# SCH_MKA-Lite-Pi-Interface.net
KiCad netlist of a schematic drawn in EasyEDA
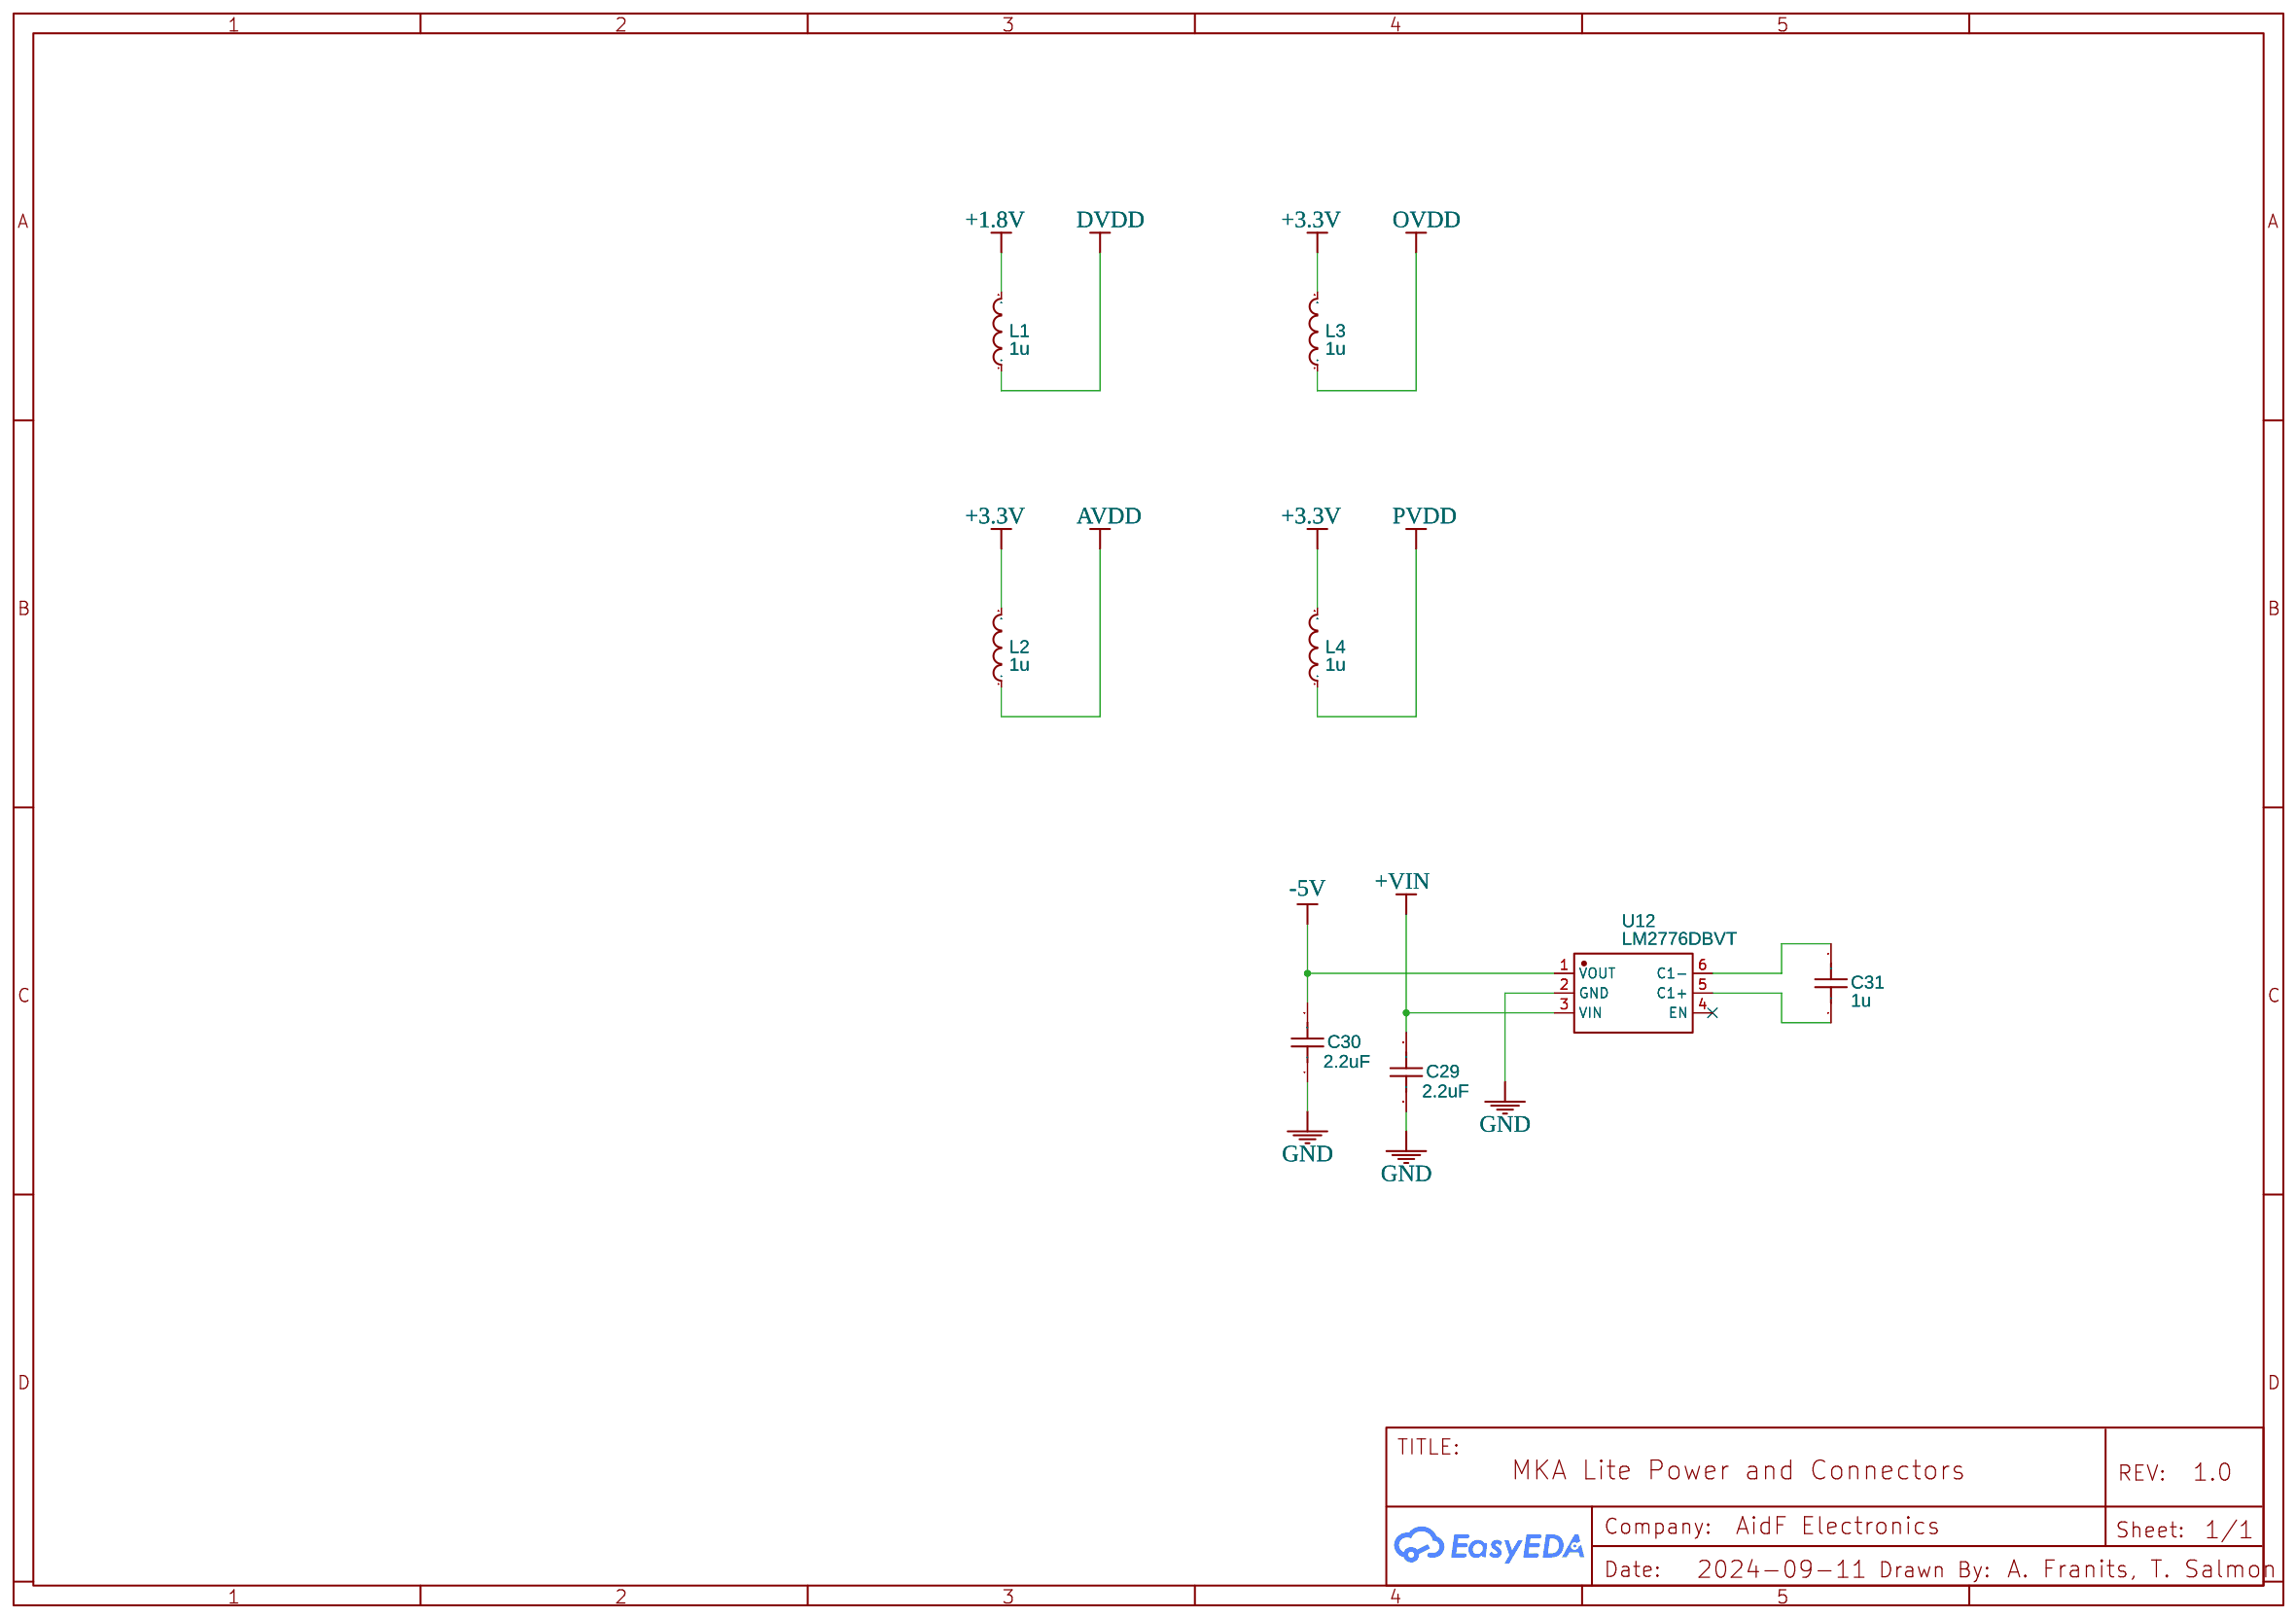
[diagram p0: Power and Connectors]
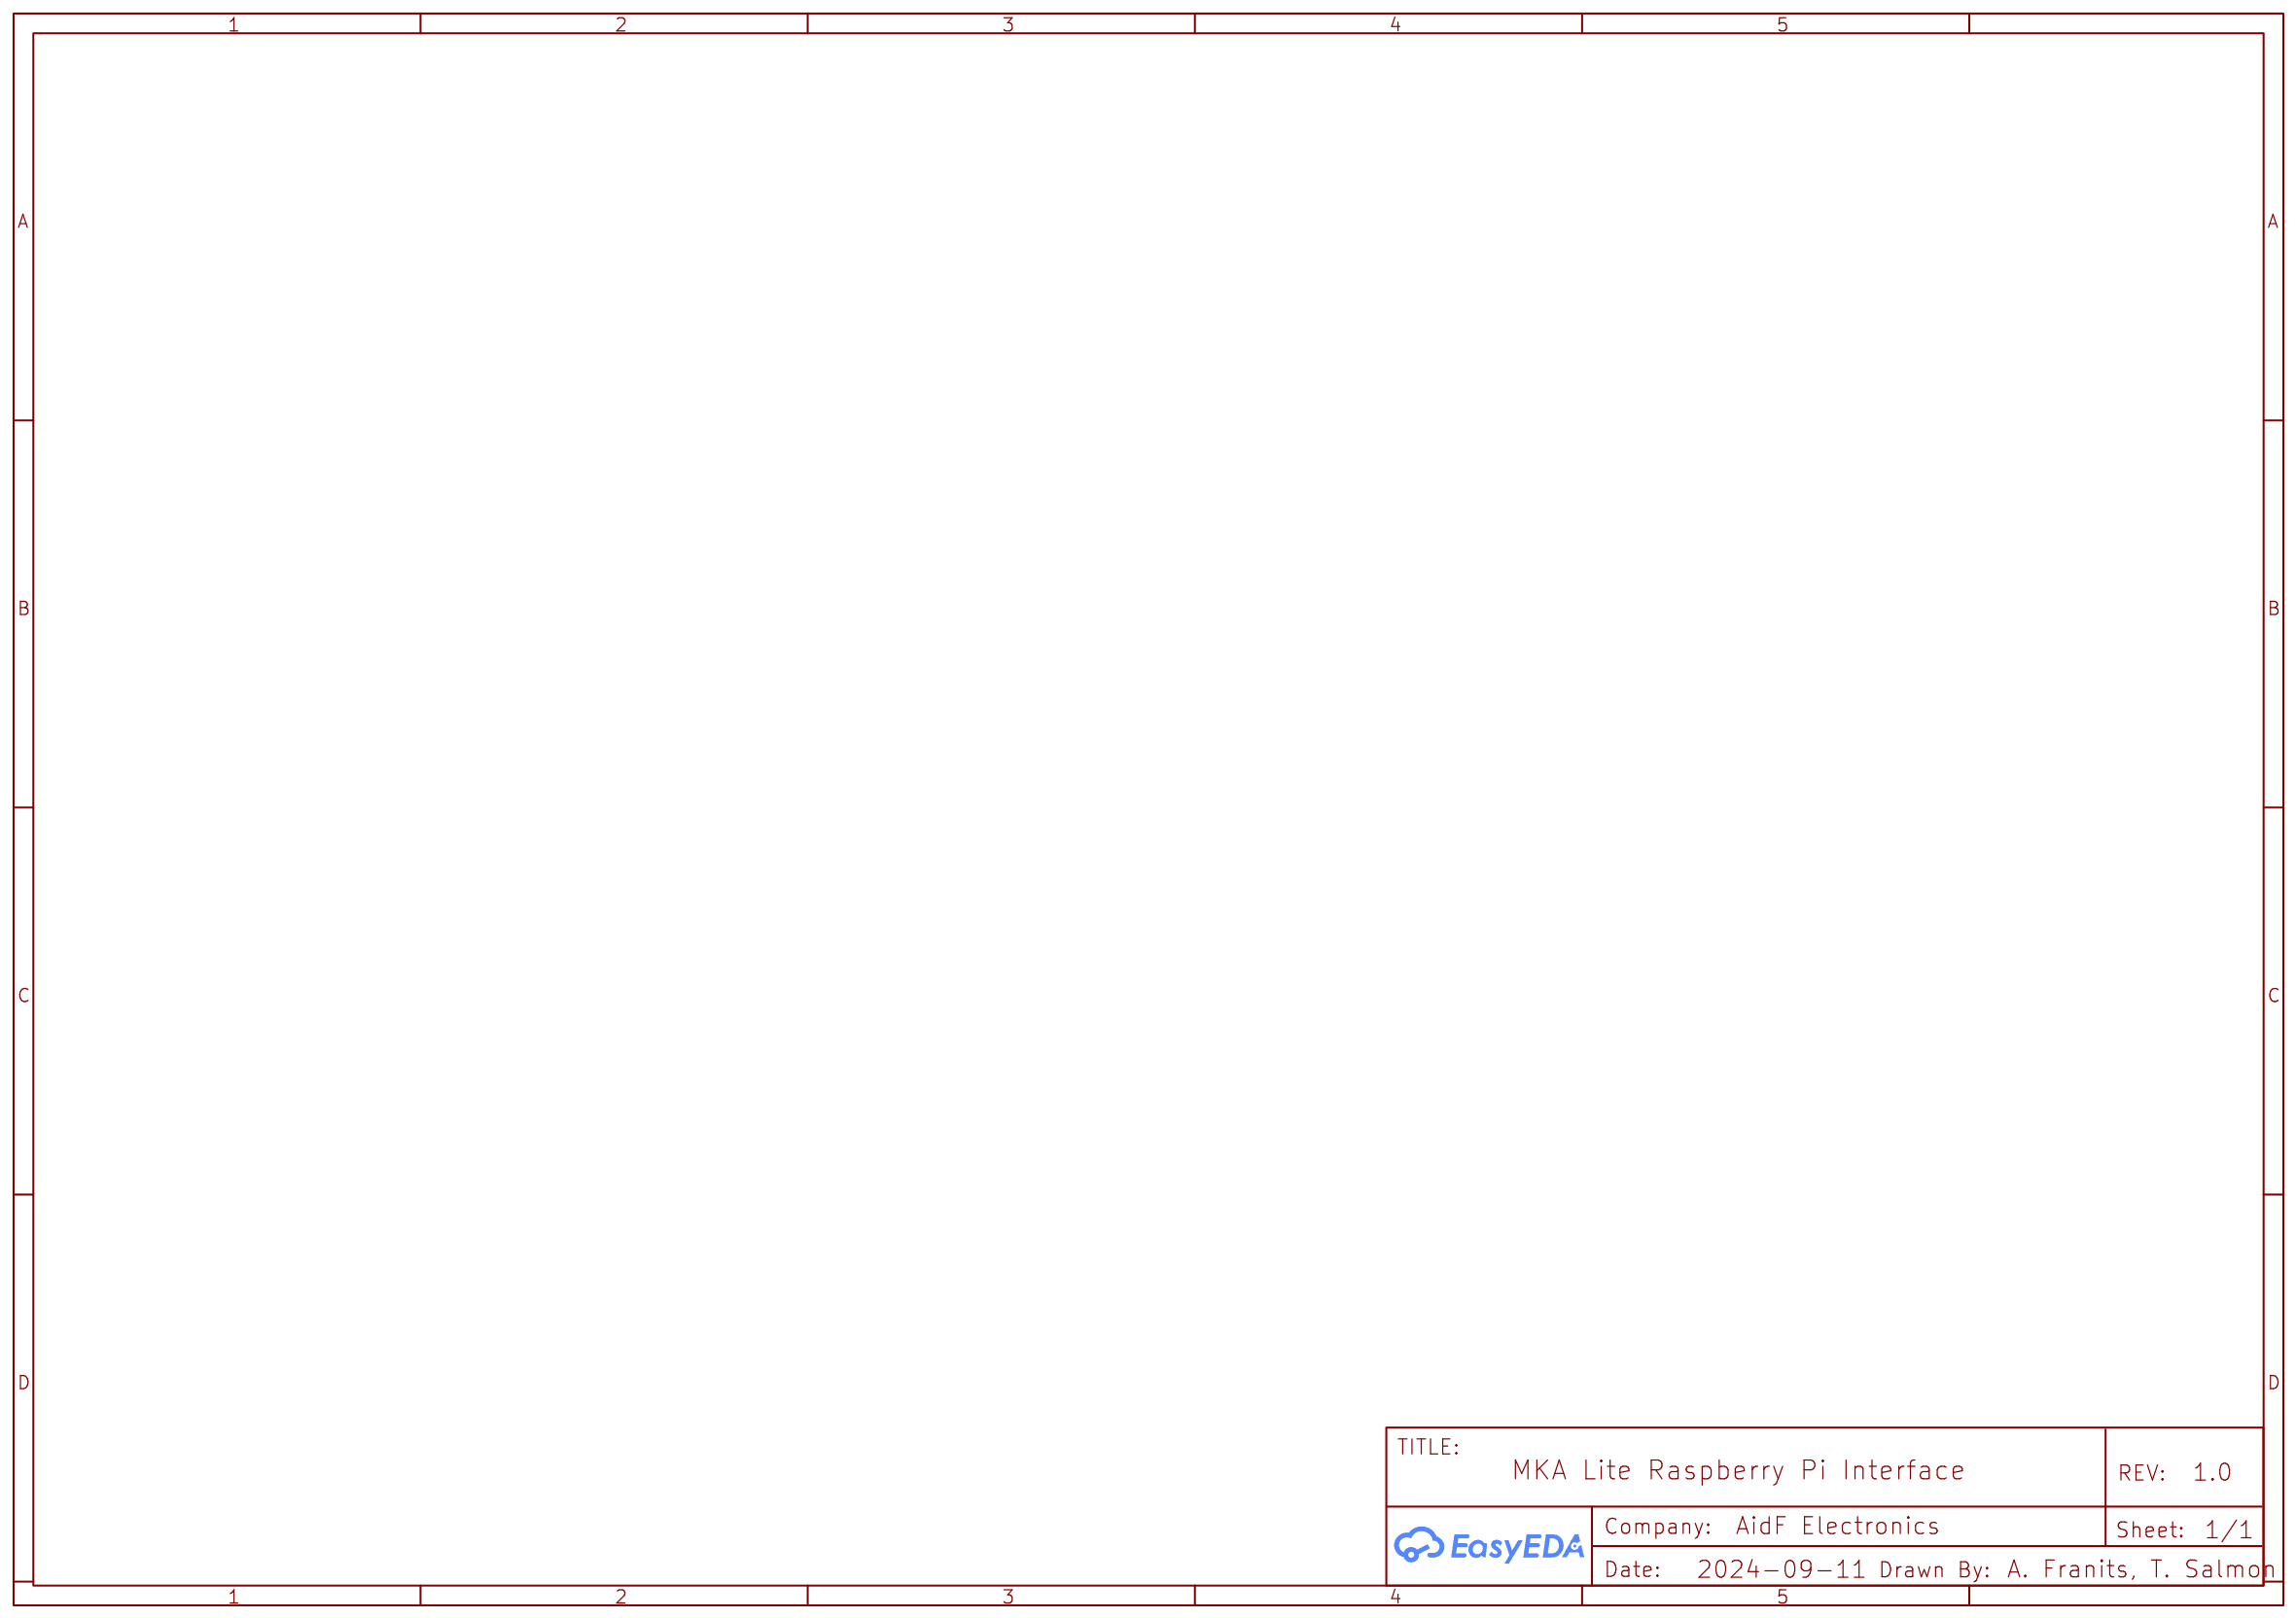
[diagram p1: Raspberry Pi CM4 Interface]
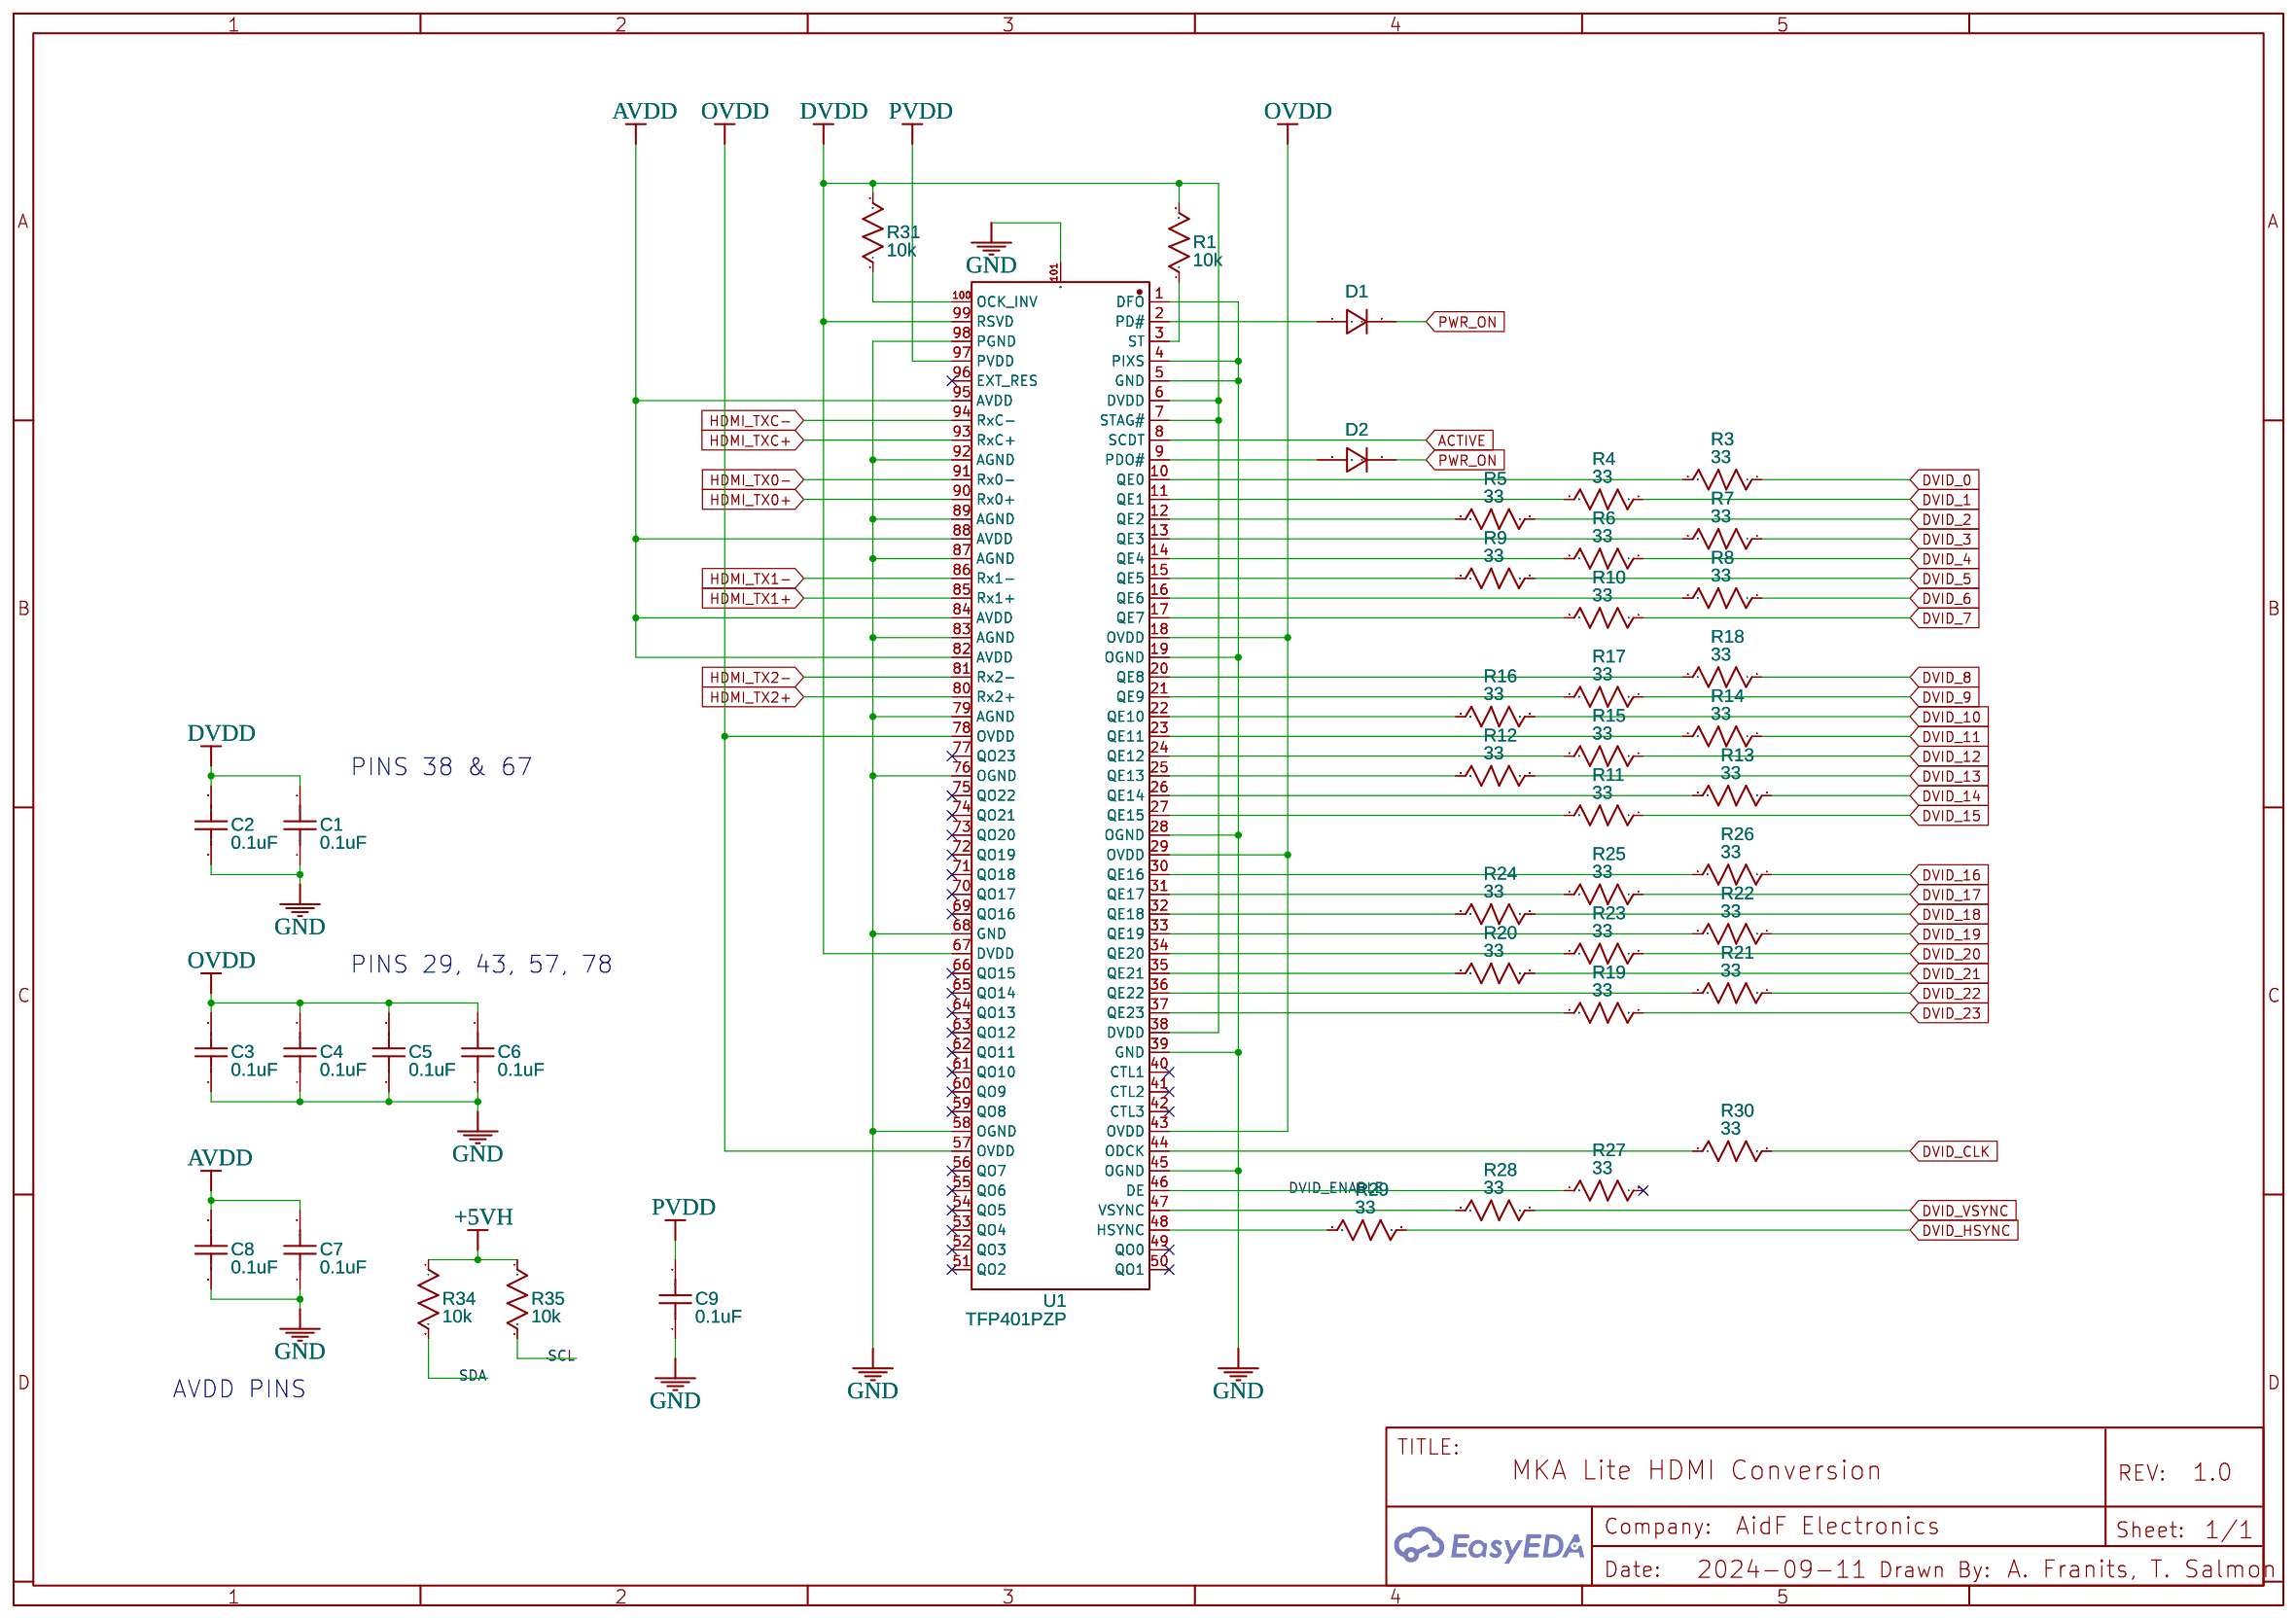
[diagram p2: HDMI Inlet]
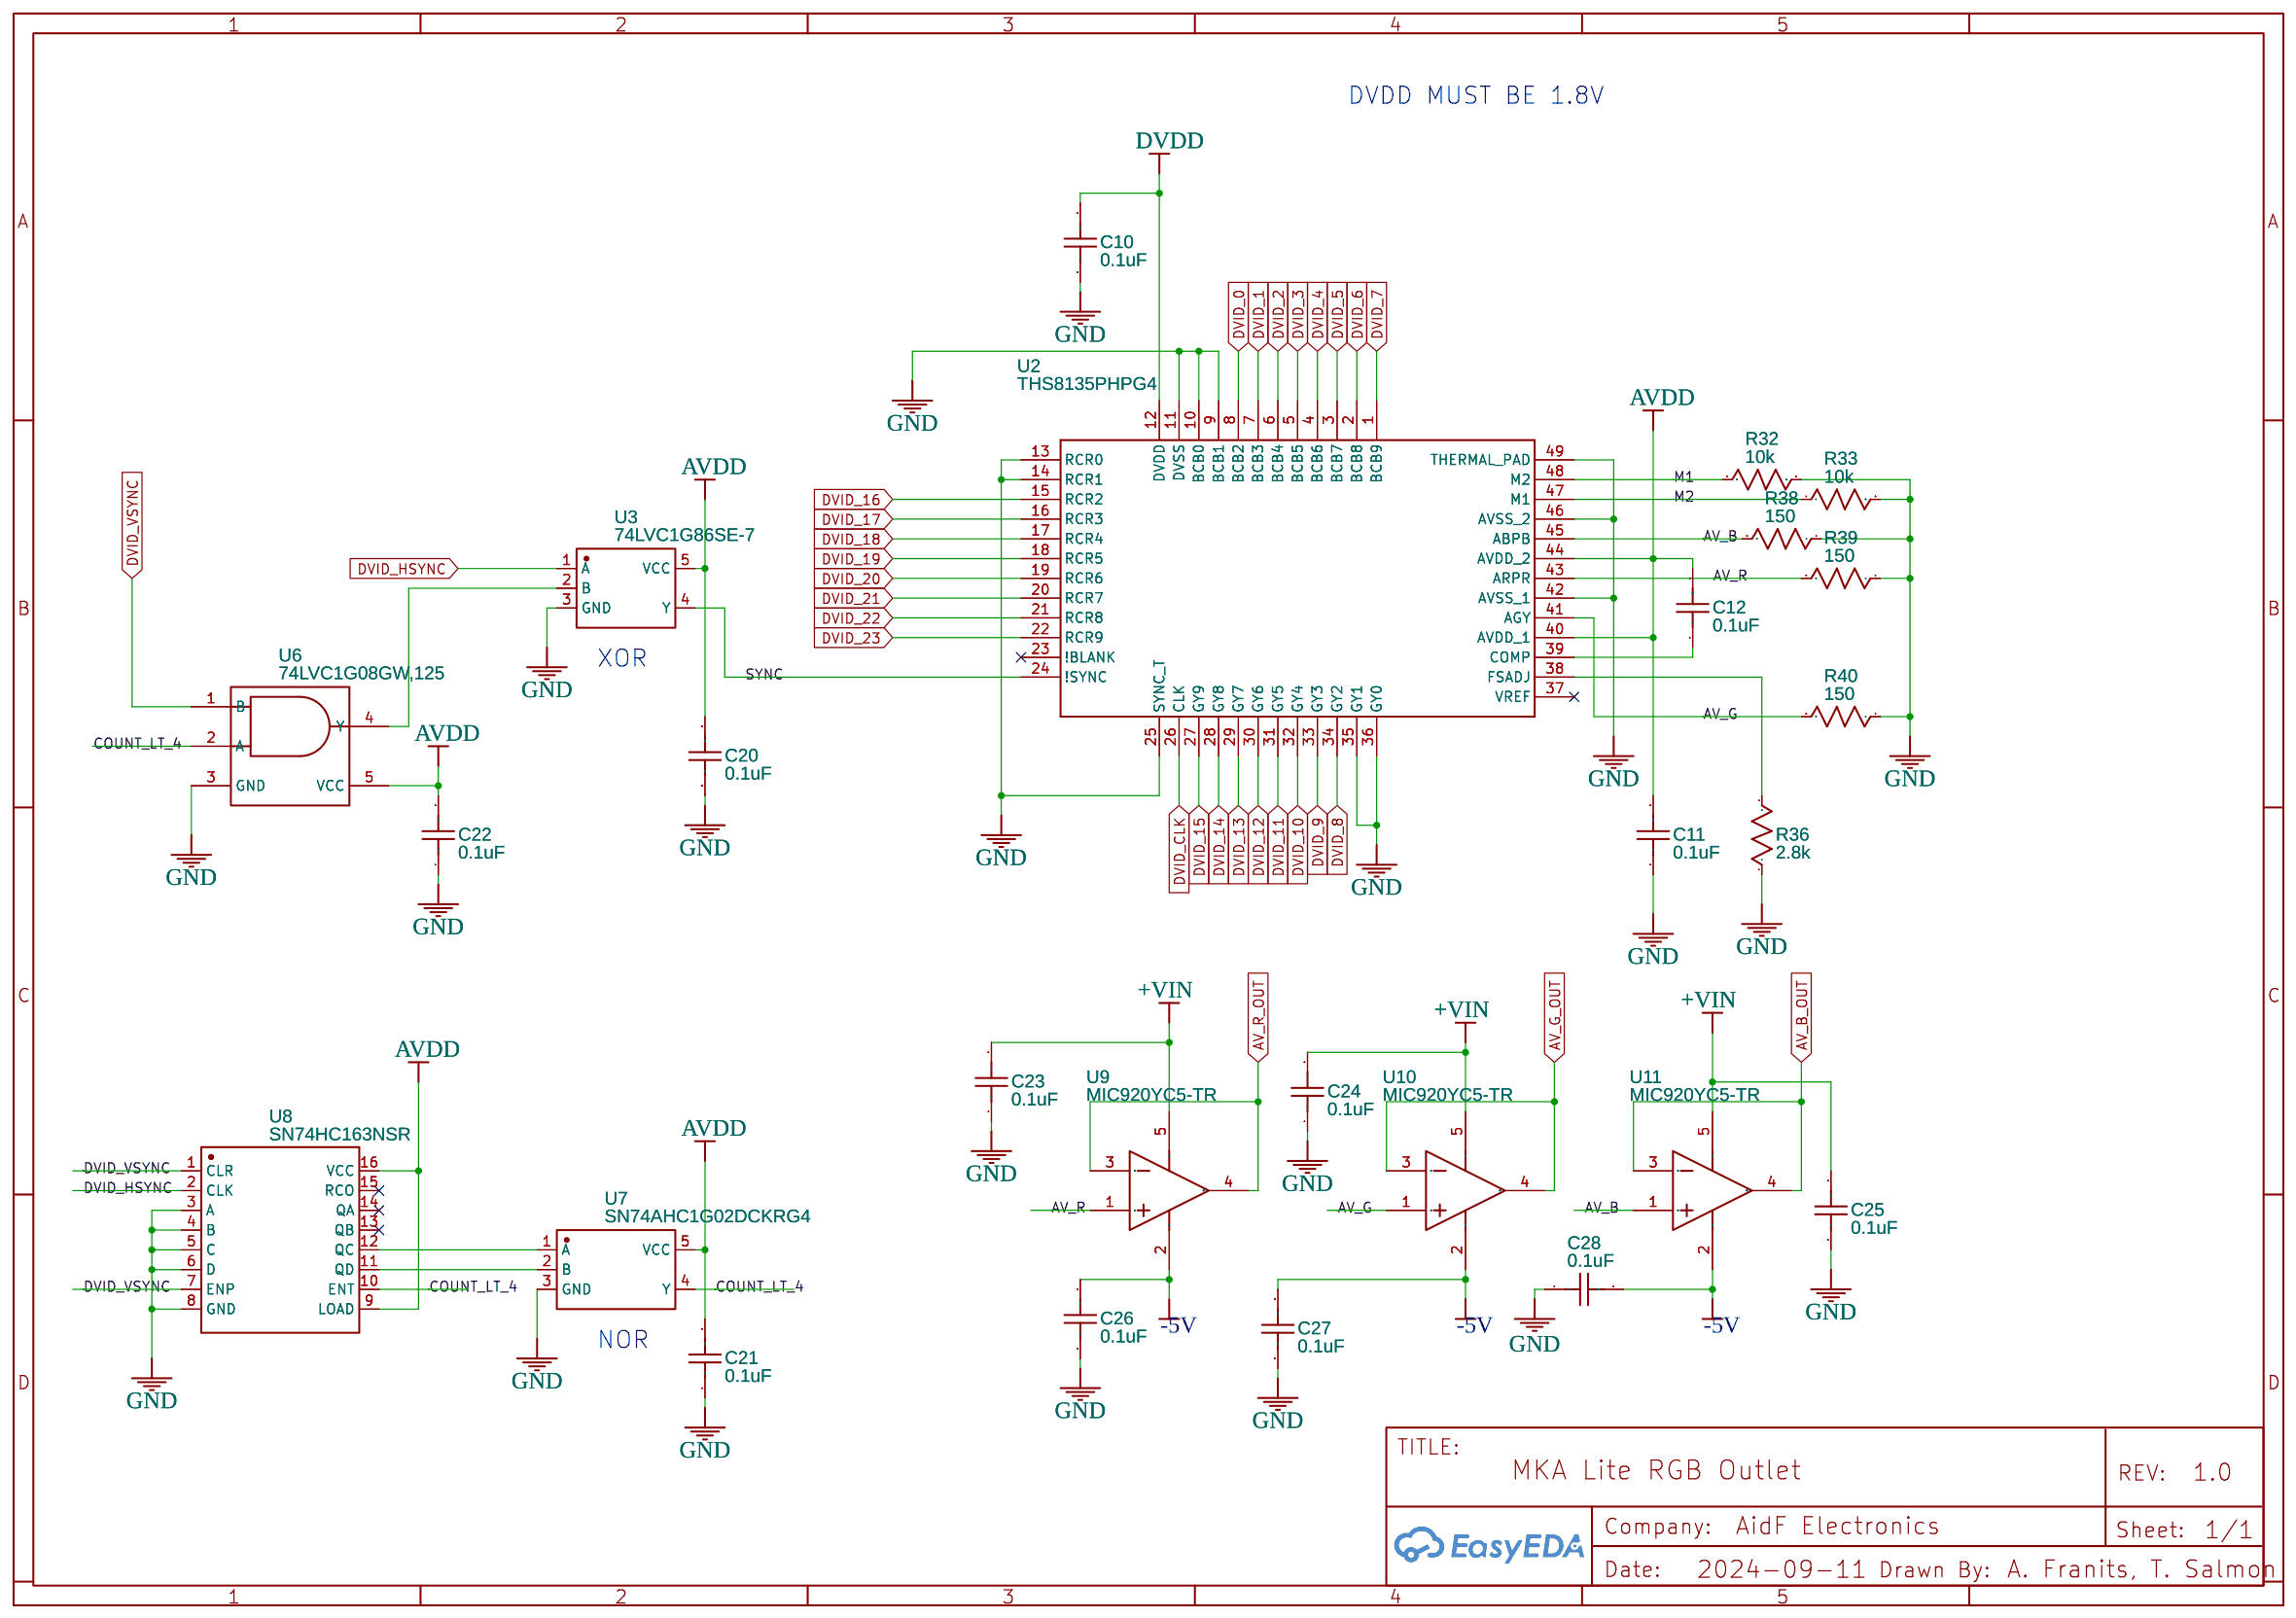
[diagram p3: RGB Outlet]
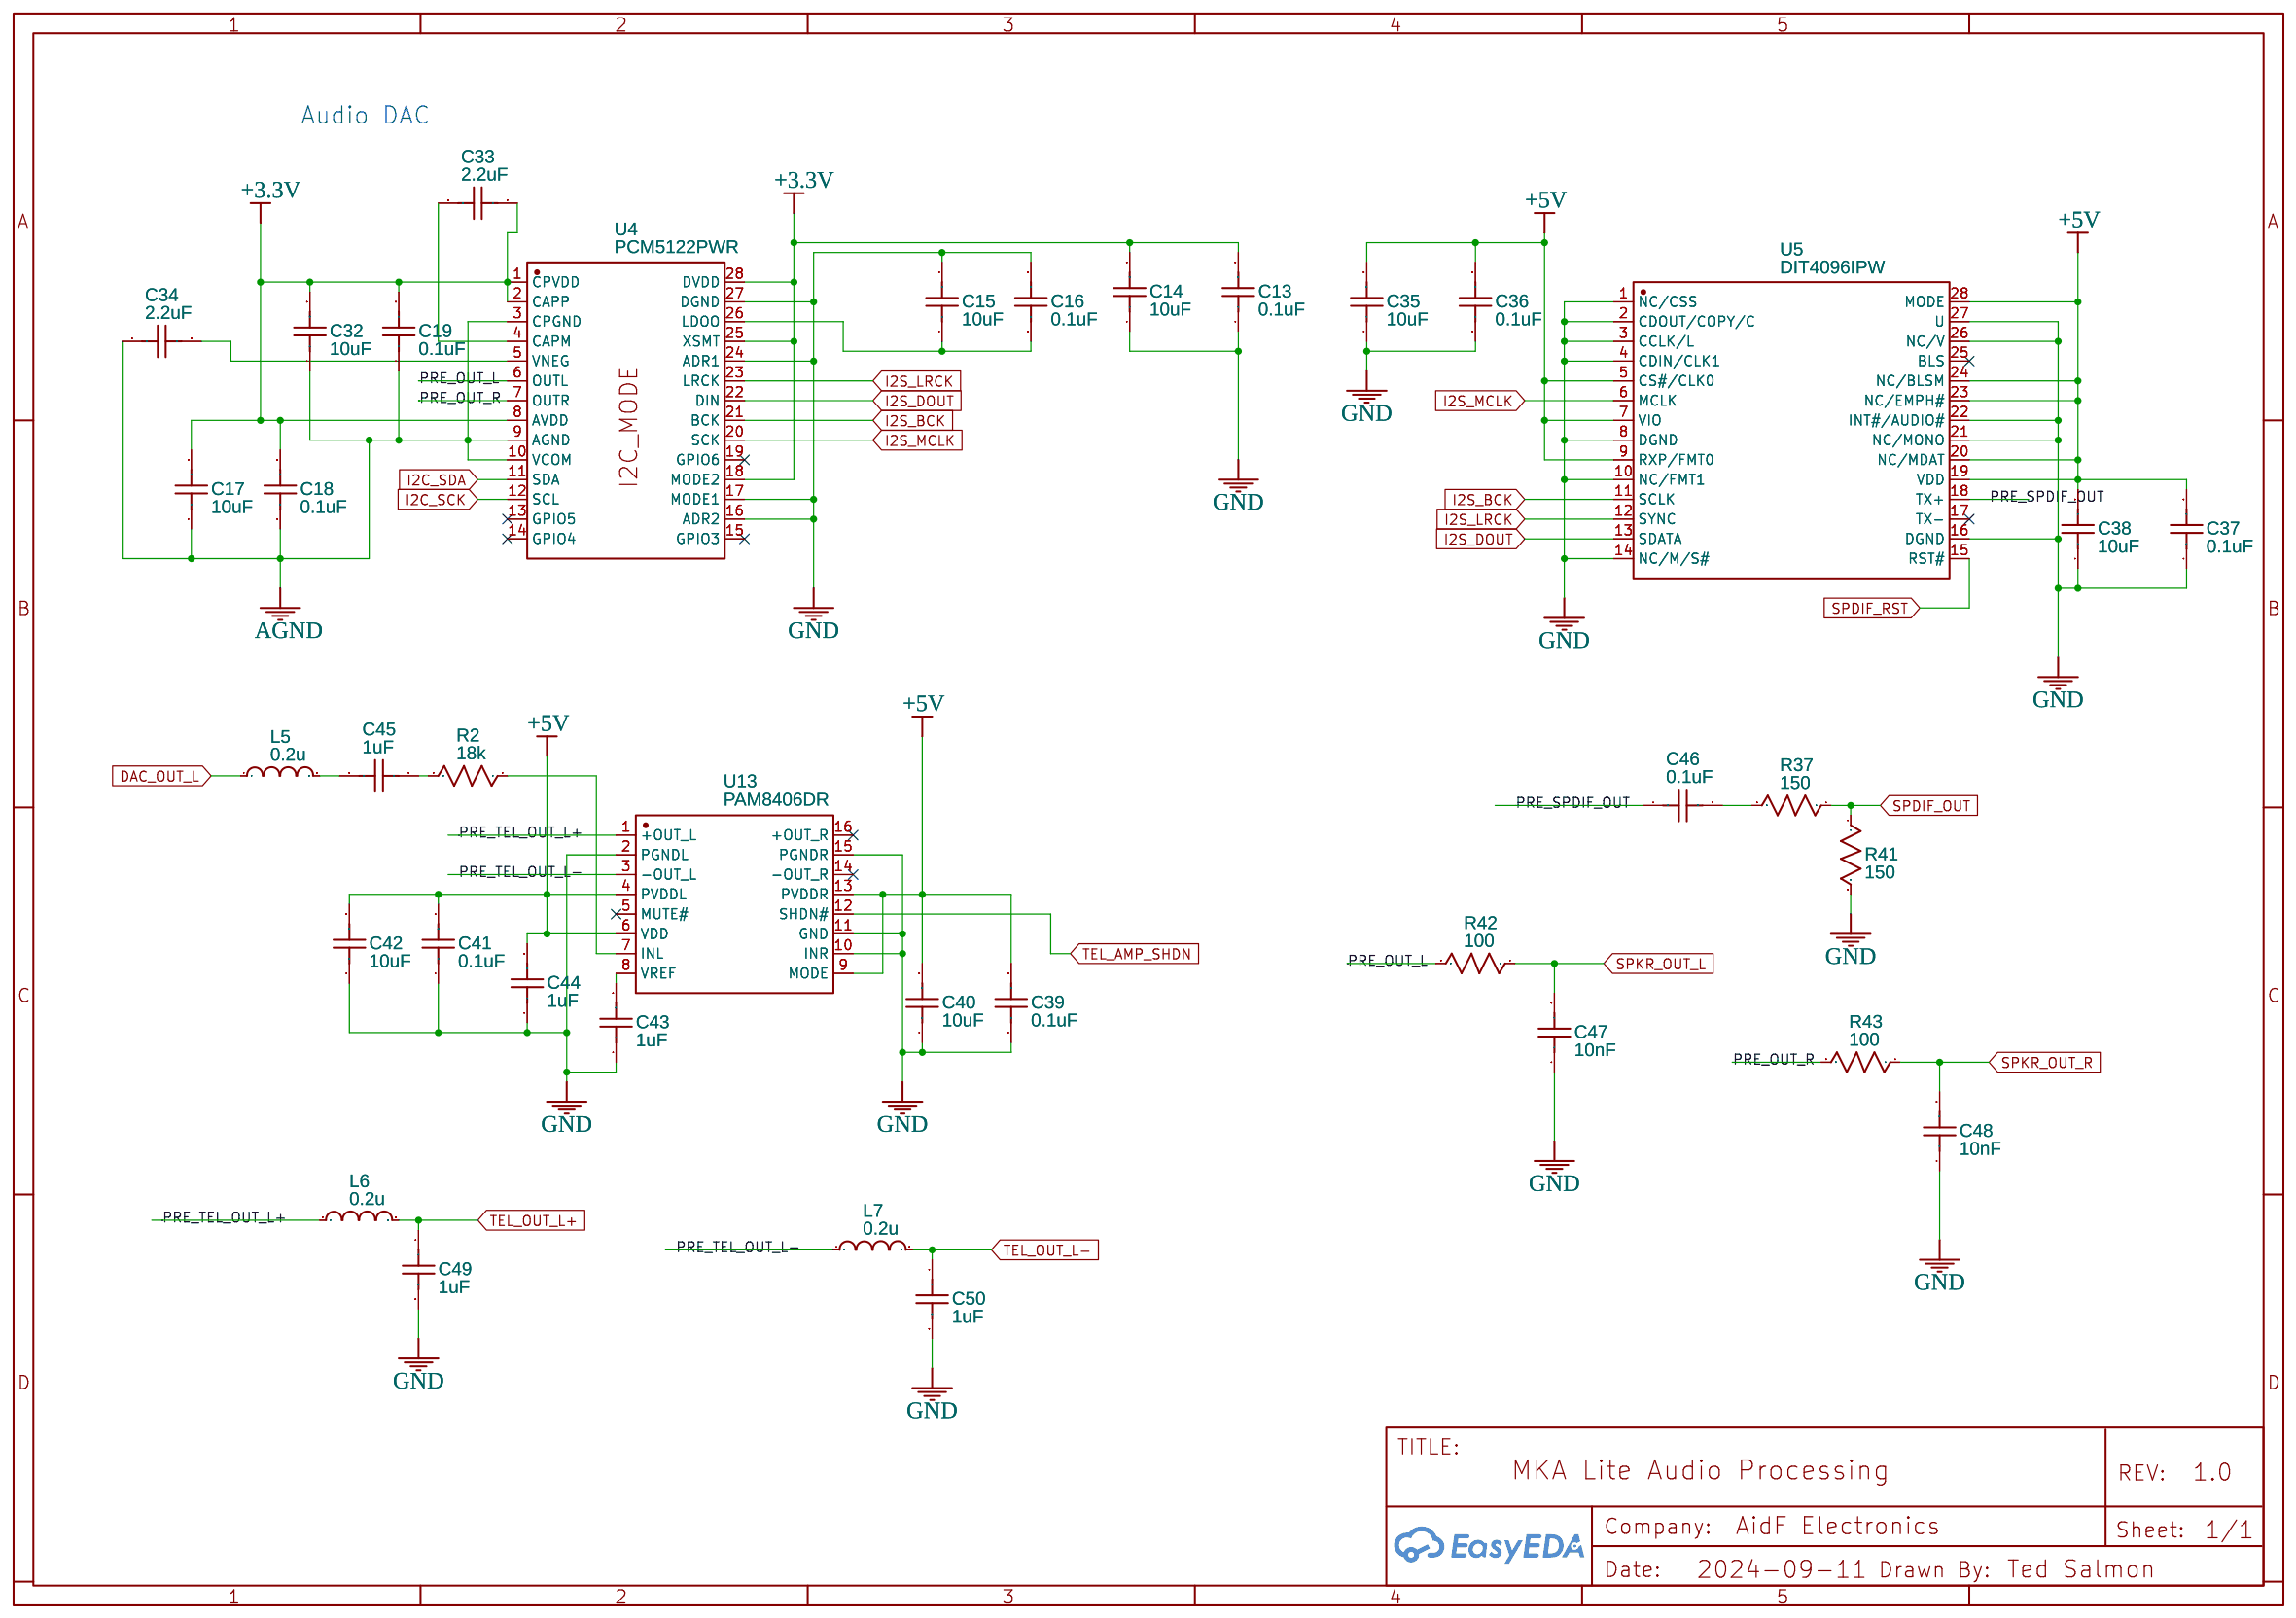
[diagram p4: Audio Processing]

(export (version "E")
  (design (tool "Eeschema 10.0.6"))
  (components
    (comp (ref "C29")
      (value "2.2uF")
      (fields
        (field (name "Manufacturer Part") "C1608X5R1E225K080AB")
        (field (name "Manufacturer") "TDK Corporation")
      )
      (libsource (lib "") (part "C_0603_US"))
    )
    (comp (ref "C30")
      (value "2.2uF")
      (fields
        (field (name "Manufacturer Part") "C1608X5R1E225K080AB")
        (field (name "Manufacturer") "TDK Corporation")
      )
      (libsource (lib "") (part "C_0603_US"))
    )
    (comp (ref "C31")
      (value "1u")
      (fields
        (field (name "Manufacturer Part") "CL10A105KB8NNNC")
        (field (name "Manufacturer") "Samsung Electro-Mechanics")
      )
      (libsource (lib "") (part "C_0603_US"))
    )
    (comp (ref "L1")
      (value "1u")
      (fields
        (field (name "Manufacturer Part") "BLM18RK601SN1D")
        (field (name "Manufacturer") "Murata Electronics")
      )
      (libsource (lib "") (part "L0603_US_1"))
    )
    (comp (ref "L2")
      (value "1u")
      (fields
        (field (name "Manufacturer Part") "BLM18RK601SN1D")
        (field (name "Manufacturer") "Murata Electronics")
      )
      (libsource (lib "") (part "L0603_US"))
    )
    (comp (ref "L3")
      (value "1u")
      (fields
        (field (name "Manufacturer Part") "BLM18RK601SN1D")
        (field (name "Manufacturer") "Murata Electronics")
      )
      (libsource (lib "") (part "L0603_US_1"))
    )
    (comp (ref "L4")
      (value "1u")
      (fields
        (field (name "Manufacturer Part") "BLM18RK601SN1D")
        (field (name "Manufacturer") "Murata Electronics")
      )
      (libsource (lib "") (part "L0603_US"))
    )
    (comp (ref "U12")
      (value "LM2776DBVT")
      (fields (field (name "Manufacturer") "TI(德州仪器)"))
      (libsource (lib "") (part "LM2776DBVT"))
    )
    (comp (ref "C1")
      (value "0.1uF")
      (fields
        (field (name "Manufacturer Part") "0603B104K101CT")
        (field (name "Manufacturer") "Walsin Technology Corporation")
      )
      (libsource (lib "") (part "C_0603_US"))
    )
    (comp (ref "C2")
      (value "0.1uF")
      (fields
        (field (name "Manufacturer Part") "0603B104K101CT")
        (field (name "Manufacturer") "Walsin Technology Corporation")
      )
      (libsource (lib "") (part "C_0603_US"))
    )
    (comp (ref "C3")
      (value "0.1uF")
      (fields
        (field (name "Manufacturer Part") "0603B104K101CT")
        (field (name "Manufacturer") "Walsin Technology Corporation")
      )
      (libsource (lib "") (part "C_0603_US"))
    )
    (comp (ref "C4")
      (value "0.1uF")
      (fields
        (field (name "Manufacturer Part") "0603B104K101CT")
        (field (name "Manufacturer") "Walsin Technology Corporation")
      )
      (libsource (lib "") (part "C_0603_US"))
    )
    (comp (ref "C5")
      (value "0.1uF")
      (fields
        (field (name "Manufacturer Part") "0603B104K101CT")
        (field (name "Manufacturer") "Walsin Technology Corporation")
      )
      (libsource (lib "") (part "C_0603_US"))
    )
    (comp (ref "C6")
      (value "0.1uF")
      (fields
        (field (name "Manufacturer Part") "0603B104K101CT")
        (field (name "Manufacturer") "Walsin Technology Corporation")
      )
      (libsource (lib "") (part "C_0603_US"))
    )
    (comp (ref "C7")
      (value "0.1uF")
      (fields
        (field (name "Manufacturer Part") "0603B104K101CT")
        (field (name "Manufacturer") "Walsin Technology Corporation")
      )
      (libsource (lib "") (part "C_0603_US"))
    )
    (comp (ref "C8")
      (value "0.1uF")
      (fields
        (field (name "Manufacturer Part") "0603B104K101CT")
        (field (name "Manufacturer") "Walsin Technology Corporation")
      )
      (libsource (lib "") (part "C_0603_US"))
    )
    (comp (ref "C9")
      (value "0.1uF")
      (fields
        (field (name "Manufacturer Part") "0603B104K101CT")
        (field (name "Manufacturer") "Walsin Technology Corporation")
      )
      (libsource (lib "") (part "C_0603_US"))
    )
    (comp (ref "D1")
      (value "SD103AWS-TP")
      (fields (field (name "Manufacturer") "Micro Commercial Co"))
      (libsource (lib "") (part "1N4148"))
    )
    (comp (ref "D2")
      (value "SD103AWS-TP")
      (fields (field (name "Manufacturer") "Micro Commercial Co"))
      (libsource (lib "") (part "1N4148"))
    )
    (comp (ref "R1")
      (value "10k")
      (fields
        (field (name "Manufacturer Part") "ESR03EZPJ103")
        (field (name "Manufacturer") "Rohm Semiconductor")
      )
      (libsource (lib "") (part "R_0603_US_2"))
    )
    (comp (ref "R3")
      (value "33")
      (fields
        (field (name "Manufacturer Part") "WR06X330 JTL")
        (field (name "Manufacturer") "Walsin Technology Corporation")
      )
      (libsource (lib "") (part "R_0603_US"))
    )
    (comp (ref "R4")
      (value "33")
      (fields
        (field (name "Manufacturer Part") "WR06X330 JTL")
        (field (name "Manufacturer") "Walsin Technology Corporation")
      )
      (libsource (lib "") (part "R_0603_US"))
    )
    (comp (ref "R5")
      (value "33")
      (fields
        (field (name "Manufacturer Part") "WR06X330 JTL")
        (field (name "Manufacturer") "Walsin Technology Corporation")
      )
      (libsource (lib "") (part "R_0603_US"))
    )
    (comp (ref "R6")
      (value "33")
      (fields
        (field (name "Manufacturer Part") "WR06X330 JTL")
        (field (name "Manufacturer") "Walsin Technology Corporation")
      )
      (libsource (lib "") (part "R_0603_US"))
    )
    (comp (ref "R7")
      (value "33")
      (fields
        (field (name "Manufacturer Part") "WR06X330 JTL")
        (field (name "Manufacturer") "Walsin Technology Corporation")
      )
      (libsource (lib "") (part "R_0603_US"))
    )
    (comp (ref "R8")
      (value "33")
      (fields
        (field (name "Manufacturer Part") "WR06X330 JTL")
        (field (name "Manufacturer") "Walsin Technology Corporation")
      )
      (libsource (lib "") (part "R_0603_US"))
    )
    (comp (ref "R9")
      (value "33")
      (fields
        (field (name "Manufacturer Part") "WR06X330 JTL")
        (field (name "Manufacturer") "Walsin Technology Corporation")
      )
      (libsource (lib "") (part "R_0603_US"))
    )
    (comp (ref "R10")
      (value "33")
      (fields
        (field (name "Manufacturer Part") "WR06X330 JTL")
        (field (name "Manufacturer") "Walsin Technology Corporation")
      )
      (libsource (lib "") (part "R_0603_US"))
    )
    (comp (ref "R11")
      (value "33")
      (fields
        (field (name "Manufacturer Part") "WR06X330 JTL")
        (field (name "Manufacturer") "Walsin Technology Corporation")
      )
      (libsource (lib "") (part "R_0603_US"))
    )
    (comp (ref "R12")
      (value "33")
      (fields
        (field (name "Manufacturer Part") "WR06X330 JTL")
        (field (name "Manufacturer") "Walsin Technology Corporation")
      )
      (libsource (lib "") (part "R_0603_US"))
    )
    (comp (ref "R13")
      (value "33")
      (fields
        (field (name "Manufacturer Part") "WR06X330 JTL")
        (field (name "Manufacturer") "Walsin Technology Corporation")
      )
      (libsource (lib "") (part "R_0603_US"))
    )
    (comp (ref "R14")
      (value "33")
      (fields
        (field (name "Manufacturer Part") "WR06X330 JTL")
        (field (name "Manufacturer") "Walsin Technology Corporation")
      )
      (libsource (lib "") (part "R_0603_US"))
    )
    (comp (ref "R15")
      (value "33")
      (fields
        (field (name "Manufacturer Part") "WR06X330 JTL")
        (field (name "Manufacturer") "Walsin Technology Corporation")
      )
      (libsource (lib "") (part "R_0603_US"))
    )
    (comp (ref "R16")
      (value "33")
      (fields
        (field (name "Manufacturer Part") "WR06X330 JTL")
        (field (name "Manufacturer") "Walsin Technology Corporation")
      )
      (libsource (lib "") (part "R_0603_US"))
    )
    (comp (ref "R17")
      (value "33")
      (fields
        (field (name "Manufacturer Part") "WR06X330 JTL")
        (field (name "Manufacturer") "Walsin Technology Corporation")
      )
      (libsource (lib "") (part "R_0603_US"))
    )
    (comp (ref "R18")
      (value "33")
      (fields
        (field (name "Manufacturer Part") "WR06X330 JTL")
        (field (name "Manufacturer") "Walsin Technology Corporation")
      )
      (libsource (lib "") (part "R_0603_US"))
    )
    (comp (ref "R19")
      (value "33")
      (fields
        (field (name "Manufacturer Part") "WR06X330 JTL")
        (field (name "Manufacturer") "Walsin Technology Corporation")
      )
      (libsource (lib "") (part "R_0603_US"))
    )
    (comp (ref "R20")
      (value "33")
      (fields
        (field (name "Manufacturer Part") "WR06X330 JTL")
        (field (name "Manufacturer") "Walsin Technology Corporation")
      )
      (libsource (lib "") (part "R_0603_US"))
    )
    (comp (ref "R21")
      (value "33")
      (fields
        (field (name "Manufacturer Part") "WR06X330 JTL")
        (field (name "Manufacturer") "Walsin Technology Corporation")
      )
      (libsource (lib "") (part "R_0603_US"))
    )
    (comp (ref "R22")
      (value "33")
      (fields
        (field (name "Manufacturer Part") "WR06X330 JTL")
        (field (name "Manufacturer") "Walsin Technology Corporation")
      )
      (libsource (lib "") (part "R_0603_US"))
    )
    (comp (ref "R23")
      (value "33")
      (fields
        (field (name "Manufacturer Part") "WR06X330 JTL")
        (field (name "Manufacturer") "Walsin Technology Corporation")
      )
      (libsource (lib "") (part "R_0603_US"))
    )
    (comp (ref "R24")
      (value "33")
      (fields
        (field (name "Manufacturer Part") "WR06X330 JTL")
        (field (name "Manufacturer") "Walsin Technology Corporation")
      )
      (libsource (lib "") (part "R_0603_US"))
    )
    (comp (ref "R25")
      (value "33")
      (fields
        (field (name "Manufacturer Part") "WR06X330 JTL")
        (field (name "Manufacturer") "Walsin Technology Corporation")
      )
      (libsource (lib "") (part "R_0603_US"))
    )
    (comp (ref "R26")
      (value "33")
      (fields
        (field (name "Manufacturer Part") "WR06X330 JTL")
        (field (name "Manufacturer") "Walsin Technology Corporation")
      )
      (libsource (lib "") (part "R_0603_US"))
    )
    (comp (ref "R27")
      (value "33")
      (fields
        (field (name "Manufacturer Part") "WR06X330 JTL")
        (field (name "Manufacturer") "Walsin Technology Corporation")
      )
      (libsource (lib "") (part "R_0603_US"))
    )
    (comp (ref "R28")
      (value "33")
      (fields
        (field (name "Manufacturer Part") "WR06X330 JTL")
        (field (name "Manufacturer") "Walsin Technology Corporation")
      )
      (libsource (lib "") (part "R_0603_US"))
    )
    (comp (ref "R29")
      (value "33")
      (fields
        (field (name "Manufacturer Part") "WR06X330 JTL")
        (field (name "Manufacturer") "Walsin Technology Corporation")
      )
      (libsource (lib "") (part "R_0603_US"))
    )
    (comp (ref "R30")
      (value "33")
      (fields
        (field (name "Manufacturer Part") "WR06X330 JTL")
        (field (name "Manufacturer") "Walsin Technology Corporation")
      )
      (libsource (lib "") (part "R_0603_US"))
    )
    (comp (ref "R31")
      (value "10k")
      (fields
        (field (name "Manufacturer Part") "ESR03EZPJ103")
        (field (name "Manufacturer") "Rohm Semiconductor")
      )
      (libsource (lib "") (part "R_0603_US_2"))
    )
    (comp (ref "R34")
      (value "10k")
      (fields
        (field (name "Manufacturer Part") "ESR03EZPJ103")
        (field (name "Manufacturer") "Rohm Semiconductor")
      )
      (libsource (lib "") (part "R_0603_US_1"))
    )
    (comp (ref "R35")
      (value "10k")
      (fields
        (field (name "Manufacturer Part") "ESR03EZPJ103")
        (field (name "Manufacturer") "Rohm Semiconductor")
      )
      (libsource (lib "") (part "R_0603_US_1"))
    )
    (comp (ref "U1")
      (value "TFP401PZP")
      (fields (field (name "Manufacturer") "Texas Instruments"))
      (libsource (lib "") (part "TFP401PZP"))
    )
    (comp (ref "C10")
      (value "0.1uF")
      (fields
        (field (name "Manufacturer Part") "0603B104K101CT")
        (field (name "Manufacturer") "Walsin Technology Corporation")
      )
      (libsource (lib "") (part "C_0603_US"))
    )
    (comp (ref "C11")
      (value "0.1uF")
      (fields
        (field (name "Manufacturer Part") "0603B104K101CT")
        (field (name "Manufacturer") "Walsin Technology Corporation")
      )
      (libsource (lib "") (part "C_0603_US"))
    )
    (comp (ref "C12")
      (value "0.1uF")
      (fields
        (field (name "Manufacturer Part") "0603B104K101CT")
        (field (name "Manufacturer") "Walsin Technology Corporation")
      )
      (libsource (lib "") (part "C_0603_US"))
    )
    (comp (ref "C20")
      (value "0.1uF")
      (fields
        (field (name "Manufacturer Part") "0603B104K101CT")
        (field (name "Manufacturer") "Walsin Technology Corporation")
      )
      (libsource (lib "") (part "C_0603_US"))
    )
    (comp (ref "C21")
      (value "0.1uF")
      (fields
        (field (name "Manufacturer Part") "0603B104K101CT")
        (field (name "Manufacturer") "Walsin Technology Corporation")
      )
      (libsource (lib "") (part "C_0603_US"))
    )
    (comp (ref "C22")
      (value "0.1uF")
      (fields
        (field (name "Manufacturer Part") "0603B104K101CT")
        (field (name "Manufacturer") "Walsin Technology Corporation")
      )
      (libsource (lib "") (part "C_0603_US"))
    )
    (comp (ref "C23")
      (value "0.1uF")
      (fields
        (field (name "Manufacturer Part") "0603B104K101CT")
        (field (name "Manufacturer") "Walsin Technology Corporation")
      )
      (libsource (lib "") (part "C_0603_US"))
    )
    (comp (ref "C24")
      (value "0.1uF")
      (fields
        (field (name "Manufacturer Part") "0603B104K101CT")
        (field (name "Manufacturer") "Walsin Technology Corporation")
      )
      (libsource (lib "") (part "C_0603_US"))
    )
    (comp (ref "C25")
      (value "0.1uF")
      (fields
        (field (name "Manufacturer Part") "0603B104K101CT")
        (field (name "Manufacturer") "Walsin Technology Corporation")
      )
      (libsource (lib "") (part "C_0603_US"))
    )
    (comp (ref "C26")
      (value "0.1uF")
      (fields
        (field (name "Manufacturer Part") "0603B104K101CT")
        (field (name "Manufacturer") "Walsin Technology Corporation")
      )
      (libsource (lib "") (part "C_0603_US"))
    )
    (comp (ref "C27")
      (value "0.1uF")
      (fields
        (field (name "Manufacturer Part") "0603B104K101CT")
        (field (name "Manufacturer") "Walsin Technology Corporation")
      )
      (libsource (lib "") (part "C_0603_US"))
    )
    (comp (ref "C28")
      (value "0.1uF")
      (fields
        (field (name "Manufacturer Part") "0603B104K101CT")
        (field (name "Manufacturer") "Walsin Technology Corporation")
      )
      (libsource (lib "") (part "C_0603_US_1"))
    )
    (comp (ref "R32")
      (value "10k")
      (fields
        (field (name "Manufacturer Part") "ESR03EZPJ103")
        (field (name "Manufacturer") "Rohm Semiconductor")
      )
      (libsource (lib "") (part "R_0603_US_1"))
    )
    (comp (ref "R33")
      (value "10k")
      (fields
        (field (name "Manufacturer Part") "ESR03EZPJ103")
        (field (name "Manufacturer") "Rohm Semiconductor")
      )
      (libsource (lib "") (part "R_0603_US_1"))
    )
    (comp (ref "R36")
      (value "2.8k")
      (fields
        (field (name "Manufacturer Part") "RMCF0603FT2K80")
        (field (name "Manufacturer") "Stackpole Electronics Inc")
      )
      (libsource (lib "") (part "R_0603_US_2"))
    )
    (comp (ref "R38")
      (value "150")
      (fields (field (name "Manufacturer Part") "RC0603FR-07150RL") (field (name "Manufacturer") "YAGEO"))
      (libsource (lib "") (part "R_0603_US"))
    )
    (comp (ref "R39")
      (value "150")
      (fields (field (name "Manufacturer Part") "RC0603FR-07150RL") (field (name "Manufacturer") "YAGEO"))
      (libsource (lib "") (part "R_0603_US"))
    )
    (comp (ref "R40")
      (value "150")
      (fields (field (name "Manufacturer Part") "RC0603FR-07150RL") (field (name "Manufacturer") "YAGEO"))
      (libsource (lib "") (part "R_0603_US"))
    )
    (comp (ref "U2")
      (value "THS8135PHPG4")
      (fields
        (field (name "Manufacturer Part") "THS8135PHP")
        (field (name "Manufacturer") "Texas Instruments")
      )
      (libsource (lib "") (part "THS8135PHPG4"))
    )
    (comp (ref "U3")
      (value "74LVC1G86SE-7")
      (fields (field (name "Manufacturer") "Diodes Incorporated"))
      (libsource (lib "") (part "74LVC1G86SE-7"))
    )
    (comp (ref "U6")
      (value "74LVC1G08GW,125")
      (fields (field (name "Manufacturer") "Nexperia USA Inc."))
      (libsource (lib "") (part "74LVC1G08GW,125"))
    )
    (comp (ref "U7")
      (value "SN74AHC1G02DCKRG4")
      (fields (field (name "Manufacturer") "TI(德州仪器)"))
      (libsource (lib "") (part "SN74AHC1G02DCKRG4"))
    )
    (comp (ref "U8")
      (value "SN74HC163NSR")
      (fields (field (name "Manufacturer") "Texas Instruments"))
      (libsource (lib "") (part "SN74HC163NSR"))
    )
    (comp (ref "U9")
      (value "MIC920YC5-TR")
      (fields (field (name "Manufacturer") "Microchip Technology"))
      (libsource (lib "") (part "MIC920YC5-TR"))
    )
    (comp (ref "U10")
      (value "MIC920YC5-TR")
      (fields (field (name "Manufacturer") "Microchip Technology"))
      (libsource (lib "") (part "MIC920YC5-TR"))
    )
    (comp (ref "U11")
      (value "MIC920YC5-TR")
      (fields (field (name "Manufacturer") "Microchip Technology"))
      (libsource (lib "") (part "MIC920YC5-TR"))
    )
    (comp (ref "C13")
      (value "0.1uF")
      (fields
        (field (name "Manufacturer Part") "0603B104K101CT")
        (field (name "Manufacturer") "Walsin Technology Corporation")
      )
      (libsource (lib "") (part "C_0603_US"))
    )
    (comp (ref "C14")
      (value "10uF")
      (fields
        (field (name "Manufacturer Part") "GRM188R61E106KA73D")
        (field (name "Manufacturer") "Murata Electronics")
      )
      (libsource (lib "") (part "C_0603_US"))
    )
    (comp (ref "C15")
      (value "10uF")
      (fields
        (field (name "Manufacturer Part") "GRM188R61E106KA73D")
        (field (name "Manufacturer") "Murata Electronics")
      )
      (libsource (lib "") (part "C_0603_US"))
    )
    (comp (ref "C16")
      (value "0.1uF")
      (fields
        (field (name "Manufacturer Part") "0603B104K101CT")
        (field (name "Manufacturer") "Walsin Technology Corporation")
      )
      (libsource (lib "") (part "C_0603_US"))
    )
    (comp (ref "C17")
      (value "10uF")
      (fields
        (field (name "Manufacturer Part") "GRM188R61E106KA73D")
        (field (name "Manufacturer") "Murata Electronics")
      )
      (libsource (lib "") (part "C_0603_US"))
    )
    (comp (ref "C18")
      (value "0.1uF")
      (fields
        (field (name "Manufacturer Part") "0603B104K101CT")
        (field (name "Manufacturer") "Walsin Technology Corporation")
      )
      (libsource (lib "") (part "C_0603_US"))
    )
    (comp (ref "C19")
      (value "0.1uF")
      (fields
        (field (name "Manufacturer Part") "0603B104K101CT")
        (field (name "Manufacturer") "Walsin Technology Corporation")
      )
      (libsource (lib "") (part "C_0603_US"))
    )
    (comp (ref "C32")
      (value "10uF")
      (fields
        (field (name "Manufacturer Part") "GRM188R61E106KA73D")
        (field (name "Manufacturer") "Murata Electronics")
      )
      (libsource (lib "") (part "C_0603_US"))
    )
    (comp (ref "C33")
      (value "2.2uF")
      (fields
        (field (name "Manufacturer Part") "GRM188R61E225KA12D")
        (field (name "Manufacturer") "Murata Electronics")
      )
      (libsource (lib "") (part "C_0603_US_3"))
    )
    (comp (ref "C34")
      (value "2.2uF")
      (fields
        (field (name "Manufacturer Part") "GRM188R61E225KA12D")
        (field (name "Manufacturer") "Murata Electronics")
      )
      (libsource (lib "") (part "C_0603_US_1"))
    )
    (comp (ref "C35")
      (value "10uF")
      (fields
        (field (name "Manufacturer Part") "GRM188R61E106KA73D")
        (field (name "Manufacturer") "Murata Electronics")
      )
      (libsource (lib "") (part "C_0603_US"))
    )
    (comp (ref "C36")
      (value "0.1uF")
      (fields
        (field (name "Manufacturer Part") "0603B104K101CT")
        (field (name "Manufacturer") "Walsin Technology Corporation")
      )
      (libsource (lib "") (part "C_0603_US"))
    )
    (comp (ref "C37")
      (value "0.1uF")
      (fields
        (field (name "Manufacturer Part") "0603B104K101CT")
        (field (name "Manufacturer") "Walsin Technology Corporation")
      )
      (libsource (lib "") (part "C_0603_US"))
    )
    (comp (ref "C38")
      (value "10uF")
      (fields
        (field (name "Manufacturer Part") "GRM188R61E106KA73D")
        (field (name "Manufacturer") "Murata Electronics")
      )
      (libsource (lib "") (part "C_0603_US"))
    )
    (comp (ref "C39")
      (value "0.1uF")
      (fields
        (field (name "Manufacturer Part") "0603B104K101CT")
        (field (name "Manufacturer") "Walsin Technology Corporation")
      )
      (libsource (lib "") (part "C_0603_US"))
    )
    (comp (ref "C40")
      (value "10uF")
      (fields
        (field (name "Manufacturer Part") "GRM188R61E106KA73D")
        (field (name "Manufacturer") "Murata Electronics")
      )
      (libsource (lib "") (part "C_0603_US"))
    )
    (comp (ref "C41")
      (value "0.1uF")
      (fields
        (field (name "Manufacturer Part") "0603B104K101CT")
        (field (name "Manufacturer") "Walsin Technology Corporation")
      )
      (libsource (lib "") (part "C_0603_US"))
    )
    (comp (ref "C42")
      (value "10uF")
      (fields
        (field (name "Manufacturer Part") "GRM188R61E106KA73D")
        (field (name "Manufacturer") "Murata Electronics")
      )
      (libsource (lib "") (part "C_0603_US"))
    )
    (comp (ref "C43")
      (value "1uF")
      (fields (field (name "Manufacturer Part") "CC0603KRX5R8BB105") (field (name "Manufacturer") "YAGEO"))
      (libsource (lib "") (part "C_0603_US"))
    )
    (comp (ref "C44")
      (value "1uF")
      (fields (field (name "Manufacturer Part") "CC0603KRX5R8BB105") (field (name "Manufacturer") "YAGEO"))
      (libsource (lib "") (part "C_0603_US"))
    )
    (comp (ref "C45")
      (value "1uF")
      (fields (field (name "Manufacturer Part") "CC0603KRX5R8BB105") (field (name "Manufacturer") "YAGEO"))
      (libsource (lib "") (part "C_0603_US_3"))
    )
    (comp (ref "C46")
      (value "0.1uF")
      (fields
        (field (name "Manufacturer Part") "0603B104K101CT")
        (field (name "Manufacturer") "Walsin Technology Corporation")
      )
      (libsource (lib "") (part "C_0603_US_1"))
    )
    (comp (ref "C47")
      (value "10nF")
      (fields
        (field (name "Manufacturer Part") "GCM188R72A103KA37D")
        (field (name "Manufacturer") "Murata Electronics")
      )
      (libsource (lib "") (part "C_0603_US"))
    )
    (comp (ref "C48")
      (value "10nF")
      (fields
        (field (name "Manufacturer Part") "GCM188R72A103KA37D")
        (field (name "Manufacturer") "Murata Electronics")
      )
      (libsource (lib "") (part "C_0603_US"))
    )
    (comp (ref "C49")
      (value "1uF")
      (fields (field (name "Manufacturer Part") "CC0603KRX5R8BB105") (field (name "Manufacturer") "YAGEO"))
      (libsource (lib "") (part "C_0603_US_2"))
    )
    (comp (ref "C50")
      (value "1uF")
      (fields (field (name "Manufacturer Part") "CC0603KRX5R8BB105") (field (name "Manufacturer") "YAGEO"))
      (libsource (lib "") (part "C_0603_US_2"))
    )
    (comp (ref "L5")
      (value "0.2u")
      (fields
        (field (name "Manufacturer Part") "BLM18RK601SN1D")
        (field (name "Manufacturer") "Murata Electronics")
      )
      (libsource (lib "") (part "L0603_US_1"))
    )
    (comp (ref "L6")
      (value "0.2u")
      (fields
        (field (name "Manufacturer Part") "BLM18RK601SN1D")
        (field (name "Manufacturer") "Murata Electronics")
      )
      (libsource (lib "") (part "L0603_US_1"))
    )
    (comp (ref "L7")
      (value "0.2u")
      (fields
        (field (name "Manufacturer Part") "BLM18RK601SN1D")
        (field (name "Manufacturer") "Murata Electronics")
      )
      (libsource (lib "") (part "L0603_US"))
    )
    (comp (ref "R2")
      (value "18k")
      (fields (field (name "Manufacturer Part") "RC0603FR-0718KL") (field (name "Manufacturer") "YAGEO"))
      (libsource (lib "") (part "R_0603_US_1"))
    )
    (comp (ref "R37")
      (value "150")
      (fields (field (name "Manufacturer Part") "RC0603JR-07150RL") (field (name "Manufacturer") "YAGEO"))
      (libsource (lib "") (part "R_0603_US_1"))
    )
    (comp (ref "R41")
      (value "150")
      (fields (field (name "Manufacturer Part") "RC0603JR-07150RL") (field (name "Manufacturer") "YAGEO"))
      (libsource (lib "") (part "R_0603_US"))
    )
    (comp (ref "R42")
      (value "100")
      (fields (field (name "Manufacturer Part") "RC0603FR-07100RL") (field (name "Manufacturer") "YAGEO"))
      (libsource (lib "") (part "R_0603_US_1"))
    )
    (comp (ref "R43")
      (value "100")
      (fields (field (name "Manufacturer Part") "RC0603FR-07100RL") (field (name "Manufacturer") "YAGEO"))
      (libsource (lib "") (part "R_0603_US_1"))
    )
    (comp (ref "U4")
      (value "PCM5122PWR")
      (fields (field (name "Manufacturer") "Texas Instruments"))
      (libsource (lib "") (part "PCM5122PWR"))
    )
    (comp (ref "U5")
      (value "DIT4096IPW")
      (fields (field (name "Manufacturer") "TI(德州仪器)"))
      (libsource (lib "") (part "DIT4096IPW"))
    )
    (comp (ref "U13")
      (value "PAM8406DR")
      (fields (field (name "Manufacturer") "Diodes Incorporated"))
      (libsource (lib "") (part "PAM8406DR"))
    )
  )
  (nets
    (net (code "1") (name "+1.8V") (class "Default")
      (node (ref "L1") (pin "2") (pinfunction "2_2") (pintype "unspecified"))
    )
    (net (code "2") (name "+3.3V") (class "Default")
      (node (ref "C13") (pin "2") (pinfunction "2_2") (pintype "unspecified"))
      (node (ref "C14") (pin "2") (pinfunction "2_2") (pintype "unspecified"))
      (node (ref "C17") (pin "2") (pinfunction "2_2") (pintype "unspecified"))
      (node (ref "C18") (pin "2") (pinfunction "2_2") (pintype "unspecified"))
      (node (ref "C19") (pin "2") (pinfunction "2_2") (pintype "unspecified"))
      (node (ref "C32") (pin "2") (pinfunction "2_2") (pintype "unspecified"))
      (node (ref "C33") (pin "1") (pinfunction "1_1") (pintype "unspecified"))
      (node (ref "L2") (pin "2") (pinfunction "2_2") (pintype "unspecified"))
      (node (ref "L3") (pin "2") (pinfunction "2_2") (pintype "unspecified"))
      (node (ref "L4") (pin "2") (pinfunction "2_2") (pintype "unspecified"))
      (node (ref "U4") (pin "1") (pinfunction "CPVDD_1") (pintype "unspecified"))
      (node (ref "U4") (pin "18") (pinfunction "MODE2_18") (pintype "unspecified"))
      (node (ref "U4") (pin "2") (pinfunction "CAPP_2") (pintype "unspecified"))
      (node (ref "U4") (pin "25") (pinfunction "XSMT_25") (pintype "unspecified"))
      (node (ref "U4") (pin "28") (pinfunction "DVDD_28") (pintype "unspecified"))
      (node (ref "U4") (pin "8") (pinfunction "AVDD_8") (pintype "unspecified"))
    )
    (net (code "3") (name "+5V") (class "Default")
      (node (ref "C35") (pin "2") (pinfunction "2_2") (pintype "unspecified"))
      (node (ref "C36") (pin "2") (pinfunction "2_2") (pintype "unspecified"))
      (node (ref "C37") (pin "2") (pinfunction "2_2") (pintype "unspecified"))
      (node (ref "C38") (pin "2") (pinfunction "2_2") (pintype "unspecified"))
      (node (ref "C39") (pin "2") (pinfunction "2_2") (pintype "unspecified"))
      (node (ref "C40") (pin "2") (pinfunction "2_2") (pintype "unspecified"))
      (node (ref "C41") (pin "2") (pinfunction "2_2") (pintype "unspecified"))
      (node (ref "C42") (pin "2") (pinfunction "2_2") (pintype "unspecified"))
      (node (ref "C44") (pin "2") (pinfunction "2_2") (pintype "unspecified"))
      (node (ref "U13") (pin "13") (pinfunction "PVDDR_13") (pintype "unspecified"))
      (node (ref "U13") (pin "4") (pinfunction "PVDDL_4") (pintype "unspecified"))
      (node (ref "U13") (pin "6") (pinfunction "VDD_6") (pintype "unspecified"))
      (node (ref "U13") (pin "9") (pinfunction "MODE_9") (pintype "unspecified"))
      (node (ref "U5") (pin "19") (pinfunction "VDD_19") (pintype "unspecified"))
      (node (ref "U5") (pin "20") (pinfunction "NC/MDAT_20") (pintype "unspecified"))
      (node (ref "U5") (pin "23") (pinfunction "NC/EMPH#_23") (pintype "unspecified"))
      (node (ref "U5") (pin "24") (pinfunction "NC/BLSM_24") (pintype "unspecified"))
      (node (ref "U5") (pin "28") (pinfunction "MODE_28") (pintype "unspecified"))
      (node (ref "U5") (pin "5") (pinfunction "CS#/CLK0_5") (pintype "unspecified"))
      (node (ref "U5") (pin "7") (pinfunction "VIO_7") (pintype "unspecified"))
      (node (ref "U5") (pin "9") (pinfunction "RXP/FMT0_9") (pintype "unspecified"))
    )
    (net (code "4") (name "+5VH") (class "Default")
      (node (ref "R34") (pin "1") (pinfunction "1_1") (pintype "unspecified"))
      (node (ref "R35") (pin "1") (pinfunction "1_1") (pintype "unspecified"))
    )
    (net (code "5") (name "+VIN") (class "Default")
      (node (ref "C23") (pin "2") (pinfunction "2_2") (pintype "unspecified"))
      (node (ref "C24") (pin "2") (pinfunction "2_2") (pintype "unspecified"))
      (node (ref "C25") (pin "2") (pinfunction "2_2") (pintype "unspecified"))
      (node (ref "C29") (pin "2") (pinfunction "2_2") (pintype "unspecified"))
      (node (ref "U10") (pin "5") (pinfunction "VDD_5") (pintype "passive"))
      (node (ref "U11") (pin "5") (pinfunction "VDD_5") (pintype "passive"))
      (node (ref "U12") (pin "3") (pinfunction "VIN_3") (pintype "unspecified"))
      (node (ref "U9") (pin "5") (pinfunction "VDD_5") (pintype "passive"))
    )
    (net (code "6") (name "-5V") (class "Default")
      (node (ref "C26") (pin "2") (pinfunction "2_2") (pintype "unspecified"))
      (node (ref "C27") (pin "2") (pinfunction "2_2") (pintype "unspecified"))
      (node (ref "C28") (pin "2") (pinfunction "2_2") (pintype "unspecified"))
      (node (ref "C30") (pin "2") (pinfunction "2_2") (pintype "unspecified"))
      (node (ref "U10") (pin "2") (pinfunction "VSS_2") (pintype "passive"))
      (node (ref "U11") (pin "2") (pinfunction "VSS_2") (pintype "passive"))
      (node (ref "U12") (pin "1") (pinfunction "VOUT_1") (pintype "unspecified"))
      (node (ref "U9") (pin "2") (pinfunction "VSS_2") (pintype "passive"))
    )
    (net (code "7") (name "ACTIVE") (class "Default")
      (node (ref "U1") (pin "8") (pinfunction "SCDT_8") (pintype "unspecified"))
    )
    (net (code "8") (name "AGND") (class "Default")
      (node (ref "C17") (pin "1") (pinfunction "1_1") (pintype "unspecified"))
      (node (ref "C18") (pin "1") (pinfunction "1_1") (pintype "unspecified"))
      (node (ref "C19") (pin "1") (pinfunction "1_1") (pintype "unspecified"))
      (node (ref "C32") (pin "1") (pinfunction "1_1") (pintype "unspecified"))
      (node (ref "C34") (pin "1") (pinfunction "1_1") (pintype "unspecified"))
      (node (ref "U4") (pin "10") (pinfunction "VCOM_10") (pintype "unspecified"))
      (node (ref "U4") (pin "3") (pinfunction "CPGND_3") (pintype "unspecified"))
      (node (ref "U4") (pin "9") (pinfunction "AGND_9") (pintype "unspecified"))
    )
    (net (code "9") (name "AVDD") (class "Default")
      (node (ref "C11") (pin "2") (pinfunction "2_2") (pintype "unspecified"))
      (node (ref "C12") (pin "2") (pinfunction "2_2") (pintype "unspecified"))
      (node (ref "C20") (pin "2") (pinfunction "2_2") (pintype "unspecified"))
      (node (ref "C21") (pin "2") (pinfunction "2_2") (pintype "unspecified"))
      (node (ref "C22") (pin "2") (pinfunction "2_2") (pintype "unspecified"))
      (node (ref "C7") (pin "2") (pinfunction "2_2") (pintype "unspecified"))
      (node (ref "C8") (pin "2") (pinfunction "2_2") (pintype "unspecified"))
      (node (ref "L2") (pin "1") (pinfunction "1_1") (pintype "unspecified"))
      (node (ref "U1") (pin "82") (pinfunction "AVDD_82") (pintype "unspecified"))
      (node (ref "U1") (pin "84") (pinfunction "AVDD_84") (pintype "unspecified"))
      (node (ref "U1") (pin "88") (pinfunction "AVDD_88") (pintype "unspecified"))
      (node (ref "U1") (pin "95") (pinfunction "AVDD_95") (pintype "unspecified"))
      (node (ref "U2") (pin "40") (pinfunction "AVDD_1_40") (pintype "bidirectional"))
      (node (ref "U2") (pin "44") (pinfunction "AVDD_2_44") (pintype "bidirectional"))
      (node (ref "U3") (pin "5") (pinfunction "VCC_5") (pintype "unspecified"))
      (node (ref "U6") (pin "5") (pinfunction "VCC_5") (pintype "unspecified"))
      (node (ref "U7") (pin "5") (pinfunction "VCC_5") (pintype "unspecified"))
      (node (ref "U8") (pin "16") (pinfunction "VCC_16") (pintype "unspecified"))
      (node (ref "U8") (pin "9") (pinfunction "LOAD_9") (pintype "unspecified"))
    )
    (net (code "10") (name "AV_B") (class "Default")
      (node (ref "R38") (pin "2") (pinfunction "2_2") (pintype "unspecified"))
      (node (ref "U11") (pin "1") (pinfunction "VIN+_1") (pintype "unspecified"))
      (node (ref "U2") (pin "45") (pinfunction "ABPB_45") (pintype "bidirectional"))
    )
    (net (code "11") (name "AV_B_OUT") (class "Default")
      (node (ref "U11") (pin "3") (pinfunction "VIN-_3") (pintype "unspecified"))
      (node (ref "U11") (pin "4") (pinfunction "VOUT_4") (pintype "output"))
    )
    (net (code "12") (name "AV_G") (class "Default")
      (node (ref "R40") (pin "2") (pinfunction "2_2") (pintype "unspecified"))
      (node (ref "U10") (pin "1") (pinfunction "VIN+_1") (pintype "unspecified"))
      (node (ref "U2") (pin "41") (pinfunction "AGY_41") (pintype "bidirectional"))
    )
    (net (code "13") (name "AV_G_OUT") (class "Default")
      (node (ref "U10") (pin "3") (pinfunction "VIN-_3") (pintype "unspecified"))
      (node (ref "U10") (pin "4") (pinfunction "VOUT_4") (pintype "output"))
    )
    (net (code "14") (name "AV_R") (class "Default")
      (node (ref "R39") (pin "2") (pinfunction "2_2") (pintype "unspecified"))
      (node (ref "U2") (pin "43") (pinfunction "ARPR_43") (pintype "bidirectional"))
      (node (ref "U9") (pin "1") (pinfunction "VIN+_1") (pintype "unspecified"))
    )
    (net (code "15") (name "AV_R_OUT") (class "Default")
      (node (ref "U9") (pin "3") (pinfunction "VIN-_3") (pintype "unspecified"))
      (node (ref "U9") (pin "4") (pinfunction "VOUT_4") (pintype "output"))
    )
    (net (code "16") (name "COUNT_LT_4") (class "Default")
      (node (ref "U6") (pin "2") (pinfunction "A_2") (pintype "unspecified"))
      (node (ref "U7") (pin "4") (pinfunction "Y_4") (pintype "unspecified"))
      (node (ref "U8") (pin "10") (pinfunction "ENT_10") (pintype "unspecified"))
    )
    (net (code "17") (name "DAC_OUT_L") (class "Default")
      (node (ref "L5") (pin "1") (pinfunction "1_1") (pintype "unspecified"))
    )
    (net (code "18") (name "DVDD") (class "Default")
      (node (ref "C1") (pin "2") (pinfunction "2_2") (pintype "unspecified"))
      (node (ref "C10") (pin "2") (pinfunction "2_2") (pintype "unspecified"))
      (node (ref "C2") (pin "2") (pinfunction "2_2") (pintype "unspecified"))
      (node (ref "L1") (pin "1") (pinfunction "1_1") (pintype "unspecified"))
      (node (ref "R1") (pin "2") (pinfunction "2_2") (pintype "unspecified"))
      (node (ref "R31") (pin "2") (pinfunction "2_2") (pintype "unspecified"))
      (node (ref "U1") (pin "38") (pinfunction "DVDD_38") (pintype "unspecified"))
      (node (ref "U1") (pin "6") (pinfunction "DVDD_6") (pintype "unspecified"))
      (node (ref "U1") (pin "67") (pinfunction "DVDD_67") (pintype "unspecified"))
      (node (ref "U1") (pin "7") (pinfunction "STAG#_7") (pintype "unspecified"))
      (node (ref "U1") (pin "99") (pinfunction "RSVD_99") (pintype "unspecified"))
      (node (ref "U2") (pin "12") (pinfunction "DVDD_12") (pintype "bidirectional"))
    )
    (net (code "19") (name "DVID_0") (class "Default")
      (node (ref "R3") (pin "1") (pinfunction "1_1") (pintype "unspecified"))
      (node (ref "U2") (pin "8") (pinfunction "BCB2_8") (pintype "bidirectional"))
    )
    (net (code "20") (name "DVID_1") (class "Default")
      (node (ref "R4") (pin "1") (pinfunction "1_1") (pintype "unspecified"))
      (node (ref "U2") (pin "7") (pinfunction "BCB3_7") (pintype "bidirectional"))
    )
    (net (code "21") (name "DVID_2") (class "Default")
      (node (ref "R5") (pin "1") (pinfunction "1_1") (pintype "unspecified"))
      (node (ref "U2") (pin "6") (pinfunction "BCB4_6") (pintype "bidirectional"))
    )
    (net (code "22") (name "DVID_3") (class "Default")
      (node (ref "R7") (pin "1") (pinfunction "1_1") (pintype "unspecified"))
      (node (ref "U2") (pin "5") (pinfunction "BCB5_5") (pintype "bidirectional"))
    )
    (net (code "23") (name "DVID_4") (class "Default")
      (node (ref "R6") (pin "1") (pinfunction "1_1") (pintype "unspecified"))
      (node (ref "U2") (pin "4") (pinfunction "BCB6_4") (pintype "bidirectional"))
    )
    (net (code "24") (name "DVID_5") (class "Default")
      (node (ref "R9") (pin "1") (pinfunction "1_1") (pintype "unspecified"))
      (node (ref "U2") (pin "3") (pinfunction "BCB7_3") (pintype "bidirectional"))
    )
    (net (code "25") (name "DVID_6") (class "Default")
      (node (ref "R8") (pin "1") (pinfunction "1_1") (pintype "unspecified"))
      (node (ref "U2") (pin "2") (pinfunction "BCB8_2") (pintype "bidirectional"))
    )
    (net (code "26") (name "DVID_7") (class "Default")
      (node (ref "R10") (pin "1") (pinfunction "1_1") (pintype "unspecified"))
      (node (ref "U2") (pin "1") (pinfunction "BCB9_1") (pintype "bidirectional"))
    )
    (net (code "27") (name "DVID_8") (class "Default")
      (node (ref "R18") (pin "1") (pinfunction "1_1") (pintype "unspecified"))
      (node (ref "U2") (pin "34") (pinfunction "GY2_34") (pintype "bidirectional"))
    )
    (net (code "28") (name "DVID_9") (class "Default")
      (node (ref "R17") (pin "1") (pinfunction "1_1") (pintype "unspecified"))
      (node (ref "U2") (pin "33") (pinfunction "GY3_33") (pintype "bidirectional"))
    )
    (net (code "29") (name "DVID_10") (class "Default")
      (node (ref "R16") (pin "1") (pinfunction "1_1") (pintype "unspecified"))
      (node (ref "U2") (pin "32") (pinfunction "GY4_32") (pintype "bidirectional"))
    )
    (net (code "30") (name "DVID_11") (class "Default")
      (node (ref "R14") (pin "1") (pinfunction "1_1") (pintype "unspecified"))
      (node (ref "U2") (pin "31") (pinfunction "GY5_31") (pintype "bidirectional"))
    )
    (net (code "31") (name "DVID_12") (class "Default")
      (node (ref "R15") (pin "1") (pinfunction "1_1") (pintype "unspecified"))
      (node (ref "U2") (pin "30") (pinfunction "GY6_30") (pintype "bidirectional"))
    )
    (net (code "32") (name "DVID_13") (class "Default")
      (node (ref "R12") (pin "1") (pinfunction "1_1") (pintype "unspecified"))
      (node (ref "U2") (pin "29") (pinfunction "GY7_29") (pintype "bidirectional"))
    )
    (net (code "33") (name "DVID_14") (class "Default")
      (node (ref "R13") (pin "1") (pinfunction "1_1") (pintype "unspecified"))
      (node (ref "U2") (pin "28") (pinfunction "GY8_28") (pintype "bidirectional"))
    )
    (net (code "34") (name "DVID_15") (class "Default")
      (node (ref "R11") (pin "1") (pinfunction "1_1") (pintype "unspecified"))
      (node (ref "U2") (pin "27") (pinfunction "GY9_27") (pintype "bidirectional"))
    )
    (net (code "35") (name "DVID_16") (class "Default")
      (node (ref "R26") (pin "1") (pinfunction "1_1") (pintype "unspecified"))
      (node (ref "U2") (pin "15") (pinfunction "RCR2_15") (pintype "bidirectional"))
    )
    (net (code "36") (name "DVID_17") (class "Default")
      (node (ref "R25") (pin "1") (pinfunction "1_1") (pintype "unspecified"))
      (node (ref "U2") (pin "16") (pinfunction "RCR3_16") (pintype "bidirectional"))
    )
    (net (code "37") (name "DVID_18") (class "Default")
      (node (ref "R24") (pin "1") (pinfunction "1_1") (pintype "unspecified"))
      (node (ref "U2") (pin "17") (pinfunction "RCR4_17") (pintype "bidirectional"))
    )
    (net (code "38") (name "DVID_19") (class "Default")
      (node (ref "R22") (pin "1") (pinfunction "1_1") (pintype "unspecified"))
      (node (ref "U2") (pin "18") (pinfunction "RCR5_18") (pintype "bidirectional"))
    )
    (net (code "39") (name "DVID_20") (class "Default")
      (node (ref "R23") (pin "1") (pinfunction "1_1") (pintype "unspecified"))
      (node (ref "U2") (pin "19") (pinfunction "RCR6_19") (pintype "bidirectional"))
    )
    (net (code "40") (name "DVID_21") (class "Default")
      (node (ref "R20") (pin "1") (pinfunction "1_1") (pintype "unspecified"))
      (node (ref "U2") (pin "20") (pinfunction "RCR7_20") (pintype "bidirectional"))
    )
    (net (code "41") (name "DVID_22") (class "Default")
      (node (ref "R21") (pin "1") (pinfunction "1_1") (pintype "unspecified"))
      (node (ref "U2") (pin "21") (pinfunction "RCR8_21") (pintype "bidirectional"))
    )
    (net (code "42") (name "DVID_23") (class "Default")
      (node (ref "R19") (pin "1") (pinfunction "1_1") (pintype "unspecified"))
      (node (ref "U2") (pin "22") (pinfunction "RCR9_22") (pintype "bidirectional"))
    )
    (net (code "43") (name "DVID_CLK") (class "Default")
      (node (ref "R30") (pin "1") (pinfunction "1_1") (pintype "unspecified"))
      (node (ref "U2") (pin "26") (pinfunction "CLK_26") (pintype "bidirectional"))
    )
    (net (code "44") (name "DVID_ENABLE") (class "Default")
      (node (ref "R27") (pin "2") (pinfunction "2_2") (pintype "unspecified"))
      (node (ref "U1") (pin "46") (pinfunction "DE_46") (pintype "unspecified"))
    )
    (net (code "45") (name "DVID_HSYNC") (class "Default")
      (node (ref "R29") (pin "1") (pinfunction "1_1") (pintype "unspecified"))
      (node (ref "U3") (pin "1") (pinfunction "A_1") (pintype "unspecified"))
      (node (ref "U8") (pin "2") (pinfunction "CLK_2") (pintype "unspecified"))
    )
    (net (code "46") (name "DVID_VSYNC") (class "Default")
      (node (ref "R28") (pin "1") (pinfunction "1_1") (pintype "unspecified"))
      (node (ref "U6") (pin "1") (pinfunction "B_1") (pintype "unspecified"))
      (node (ref "U8") (pin "1") (pinfunction "CLR_1") (pintype "unspecified"))
      (node (ref "U8") (pin "7") (pinfunction "ENP_7") (pintype "unspecified"))
    )
    (net (code "47") (name "GND") (class "Default")
      (node (ref "C1") (pin "1") (pinfunction "1_1") (pintype "unspecified"))
      (node (ref "C10") (pin "1") (pinfunction "1_1") (pintype "unspecified"))
      (node (ref "C11") (pin "1") (pinfunction "1_1") (pintype "unspecified"))
      (node (ref "C13") (pin "1") (pinfunction "1_1") (pintype "unspecified"))
      (node (ref "C14") (pin "1") (pinfunction "1_1") (pintype "unspecified"))
      (node (ref "C15") (pin "2") (pinfunction "2_2") (pintype "unspecified"))
      (node (ref "C16") (pin "2") (pinfunction "2_2") (pintype "unspecified"))
      (node (ref "C2") (pin "1") (pinfunction "1_1") (pintype "unspecified"))
      (node (ref "C20") (pin "1") (pinfunction "1_1") (pintype "unspecified"))
      (node (ref "C21") (pin "1") (pinfunction "1_1") (pintype "unspecified"))
      (node (ref "C22") (pin "1") (pinfunction "1_1") (pintype "unspecified"))
      (node (ref "C23") (pin "1") (pinfunction "1_1") (pintype "unspecified"))
      (node (ref "C24") (pin "1") (pinfunction "1_1") (pintype "unspecified"))
      (node (ref "C25") (pin "1") (pinfunction "1_1") (pintype "unspecified"))
      (node (ref "C26") (pin "1") (pinfunction "1_1") (pintype "unspecified"))
      (node (ref "C27") (pin "1") (pinfunction "1_1") (pintype "unspecified"))
      (node (ref "C28") (pin "1") (pinfunction "1_1") (pintype "unspecified"))
      (node (ref "C29") (pin "1") (pinfunction "1_1") (pintype "unspecified"))
      (node (ref "C3") (pin "1") (pinfunction "1_1") (pintype "unspecified"))
      (node (ref "C30") (pin "1") (pinfunction "1_1") (pintype "unspecified"))
      (node (ref "C35") (pin "1") (pinfunction "1_1") (pintype "unspecified"))
      (node (ref "C36") (pin "1") (pinfunction "1_1") (pintype "unspecified"))
      (node (ref "C37") (pin "1") (pinfunction "1_1") (pintype "unspecified"))
      (node (ref "C38") (pin "1") (pinfunction "1_1") (pintype "unspecified"))
      (node (ref "C39") (pin "1") (pinfunction "1_1") (pintype "unspecified"))
      (node (ref "C4") (pin "1") (pinfunction "1_1") (pintype "unspecified"))
      (node (ref "C40") (pin "1") (pinfunction "1_1") (pintype "unspecified"))
      (node (ref "C41") (pin "1") (pinfunction "1_1") (pintype "unspecified"))
      (node (ref "C42") (pin "1") (pinfunction "1_1") (pintype "unspecified"))
      (node (ref "C43") (pin "1") (pinfunction "1_1") (pintype "unspecified"))
      (node (ref "C44") (pin "1") (pinfunction "1_1") (pintype "unspecified"))
      (node (ref "C47") (pin "1") (pinfunction "1_1") (pintype "unspecified"))
      (node (ref "C48") (pin "1") (pinfunction "1_1") (pintype "unspecified"))
      (node (ref "C49") (pin "2") (pinfunction "2_2") (pintype "unspecified"))
      (node (ref "C5") (pin "1") (pinfunction "1_1") (pintype "unspecified"))
      (node (ref "C50") (pin "2") (pinfunction "2_2") (pintype "unspecified"))
      (node (ref "C6") (pin "1") (pinfunction "1_1") (pintype "unspecified"))
      (node (ref "C7") (pin "1") (pinfunction "1_1") (pintype "unspecified"))
      (node (ref "C8") (pin "1") (pinfunction "1_1") (pintype "unspecified"))
      (node (ref "C9") (pin "1") (pinfunction "1_1") (pintype "unspecified"))
      (node (ref "R32") (pin "2") (pinfunction "2_2") (pintype "unspecified"))
      (node (ref "R33") (pin "2") (pinfunction "2_2") (pintype "unspecified"))
      (node (ref "R36") (pin "1") (pinfunction "1_1") (pintype "unspecified"))
      (node (ref "R38") (pin "1") (pinfunction "1_1") (pintype "unspecified"))
      (node (ref "R39") (pin "1") (pinfunction "1_1") (pintype "unspecified"))
      (node (ref "R40") (pin "1") (pinfunction "1_1") (pintype "unspecified"))
      (node (ref "R41") (pin "2") (pinfunction "2_2") (pintype "unspecified"))
      (node (ref "U1") (pin "1") (pinfunction "DFO_1") (pintype "unspecified"))
      (node (ref "U1") (pin "101") (pinfunction "PAD_101") (pintype "unspecified"))
      (node (ref "U1") (pin "19") (pinfunction "OGND_19") (pintype "unspecified"))
      (node (ref "U1") (pin "28") (pinfunction "OGND_28") (pintype "unspecified"))
      (node (ref "U1") (pin "39") (pinfunction "GND_39") (pintype "unspecified"))
      (node (ref "U1") (pin "4") (pinfunction "PIXS_4") (pintype "unspecified"))
      (node (ref "U1") (pin "45") (pinfunction "OGND_45") (pintype "unspecified"))
      (node (ref "U1") (pin "5") (pinfunction "GND_5") (pintype "unspecified"))
      (node (ref "U1") (pin "58") (pinfunction "OGND_58") (pintype "unspecified"))
      (node (ref "U1") (pin "68") (pinfunction "GND_68") (pintype "unspecified"))
      (node (ref "U1") (pin "76") (pinfunction "OGND_76") (pintype "unspecified"))
      (node (ref "U1") (pin "79") (pinfunction "AGND_79") (pintype "unspecified"))
      (node (ref "U1") (pin "83") (pinfunction "AGND_83") (pintype "unspecified"))
      (node (ref "U1") (pin "87") (pinfunction "AGND_87") (pintype "unspecified"))
      (node (ref "U1") (pin "89") (pinfunction "AGND_89") (pintype "unspecified"))
      (node (ref "U1") (pin "92") (pinfunction "AGND_92") (pintype "unspecified"))
      (node (ref "U1") (pin "98") (pinfunction "PGND_98") (pintype "unspecified"))
      (node (ref "U12") (pin "2") (pinfunction "GND_2") (pintype "unspecified"))
      (node (ref "U13") (pin "10") (pinfunction "INR_10") (pintype "unspecified"))
      (node (ref "U13") (pin "11") (pinfunction "GND_11") (pintype "unspecified"))
      (node (ref "U13") (pin "15") (pinfunction "PGNDR_15") (pintype "unspecified"))
      (node (ref "U13") (pin "2") (pinfunction "PGNDL_2") (pintype "unspecified"))
      (node (ref "U2") (pin "10") (pinfunction "BCB0_10") (pintype "bidirectional"))
      (node (ref "U2") (pin "11") (pinfunction "DVSS_11") (pintype "bidirectional"))
      (node (ref "U2") (pin "13") (pinfunction "RCR0_13") (pintype "bidirectional"))
      (node (ref "U2") (pin "14") (pinfunction "RCR1_14") (pintype "bidirectional"))
      (node (ref "U2") (pin "25") (pinfunction "SYNC_T_25") (pintype "bidirectional"))
      (node (ref "U2") (pin "35") (pinfunction "GY1_35") (pintype "bidirectional"))
      (node (ref "U2") (pin "36") (pinfunction "GY0_36") (pintype "bidirectional"))
      (node (ref "U2") (pin "42") (pinfunction "AVSS_1_42") (pintype "bidirectional"))
      (node (ref "U2") (pin "46") (pinfunction "AVSS_2_46") (pintype "bidirectional"))
      (node (ref "U2") (pin "49") (pinfunction "THERMAL_PAD_49") (pintype "bidirectional"))
      (node (ref "U2") (pin "9") (pinfunction "BCB1_9") (pintype "bidirectional"))
      (node (ref "U3") (pin "3") (pinfunction "GND_3") (pintype "unspecified"))
      (node (ref "U4") (pin "16") (pinfunction "ADR2_16") (pintype "unspecified"))
      (node (ref "U4") (pin "17") (pinfunction "MODE1_17") (pintype "unspecified"))
      (node (ref "U4") (pin "24") (pinfunction "ADR1_24") (pintype "unspecified"))
      (node (ref "U4") (pin "27") (pinfunction "DGND_27") (pintype "unspecified"))
      (node (ref "U5") (pin "1") (pinfunction "NC/CSS_1") (pintype "unspecified"))
      (node (ref "U5") (pin "10") (pinfunction "NC/FMT1_10") (pintype "unspecified"))
      (node (ref "U5") (pin "14") (pinfunction "NC/M/S#_14") (pintype "unspecified"))
      (node (ref "U5") (pin "16") (pinfunction "DGND_16") (pintype "unspecified"))
      (node (ref "U5") (pin "2") (pinfunction "CDOUT/COPY/C_2") (pintype "unspecified"))
      (node (ref "U5") (pin "21") (pinfunction "NC/MONO_21") (pintype "unspecified"))
      (node (ref "U5") (pin "22") (pinfunction "INT#/AUDIO#_22") (pintype "unspecified"))
      (node (ref "U5") (pin "26") (pinfunction "NC/V_26") (pintype "unspecified"))
      (node (ref "U5") (pin "27") (pinfunction "U_27") (pintype "unspecified"))
      (node (ref "U5") (pin "3") (pinfunction "CCLK/L_3") (pintype "unspecified"))
      (node (ref "U5") (pin "4") (pinfunction "CDIN/CLK1_4") (pintype "unspecified"))
      (node (ref "U5") (pin "8") (pinfunction "DGND_8") (pintype "unspecified"))
      (node (ref "U6") (pin "3") (pinfunction "GND_3") (pintype "unspecified"))
      (node (ref "U7") (pin "3") (pinfunction "GND_3") (pintype "unspecified"))
      (node (ref "U8") (pin "3") (pinfunction "A_3") (pintype "unspecified"))
      (node (ref "U8") (pin "4") (pinfunction "B_4") (pintype "unspecified"))
      (node (ref "U8") (pin "5") (pinfunction "C_5") (pintype "unspecified"))
      (node (ref "U8") (pin "6") (pinfunction "D_6") (pintype "unspecified"))
      (node (ref "U8") (pin "8") (pinfunction "GND_8") (pintype "unspecified"))
    )
    (net (code "48") (name "HDMI_TX0+") (class "Default")
      (node (ref "U1") (pin "90") (pinfunction "Rx0+_90") (pintype "unspecified"))
    )
    (net (code "49") (name "HDMI_TX0-") (class "Default")
      (node (ref "U1") (pin "91") (pinfunction "Rx0-_91") (pintype "unspecified"))
    )
    (net (code "50") (name "HDMI_TX1+") (class "Default")
      (node (ref "U1") (pin "85") (pinfunction "Rx1+_85") (pintype "unspecified"))
    )
    (net (code "51") (name "HDMI_TX1-") (class "Default")
      (node (ref "U1") (pin "86") (pinfunction "Rx1-_86") (pintype "unspecified"))
    )
    (net (code "52") (name "HDMI_TX2+") (class "Default")
      (node (ref "U1") (pin "80") (pinfunction "Rx2+_80") (pintype "unspecified"))
    )
    (net (code "53") (name "HDMI_TX2-") (class "Default")
      (node (ref "U1") (pin "81") (pinfunction "Rx2-_81") (pintype "unspecified"))
    )
    (net (code "54") (name "HDMI_TXC+") (class "Default")
      (node (ref "U1") (pin "93") (pinfunction "RxC+_93") (pintype "unspecified"))
    )
    (net (code "55") (name "HDMI_TXC-") (class "Default")
      (node (ref "U1") (pin "94") (pinfunction "RxC-_94") (pintype "unspecified"))
    )
    (net (code "56") (name "I2C_SCK") (class "Default")
      (node (ref "U4") (pin "12") (pinfunction "SCL_12") (pintype "unspecified"))
    )
    (net (code "57") (name "I2C_SDA") (class "Default")
      (node (ref "U4") (pin "11") (pinfunction "SDA_11") (pintype "unspecified"))
    )
    (net (code "58") (name "I2S_BCK") (class "Default")
      (node (ref "U4") (pin "21") (pinfunction "BCK_21") (pintype "unspecified"))
      (node (ref "U5") (pin "11") (pinfunction "SCLK_11") (pintype "unspecified"))
    )
    (net (code "59") (name "I2S_DOUT") (class "Default")
      (node (ref "U4") (pin "22") (pinfunction "DIN_22") (pintype "unspecified"))
      (node (ref "U5") (pin "13") (pinfunction "SDATA_13") (pintype "unspecified"))
    )
    (net (code "60") (name "I2S_LRCK") (class "Default")
      (node (ref "U4") (pin "23") (pinfunction "LRCK_23") (pintype "unspecified"))
      (node (ref "U5") (pin "12") (pinfunction "SYNC_12") (pintype "unspecified"))
    )
    (net (code "61") (name "I2S_MCLK") (class "Default")
      (node (ref "U4") (pin "20") (pinfunction "SCK_20") (pintype "unspecified"))
      (node (ref "U5") (pin "6") (pinfunction "MCLK_6") (pintype "unspecified"))
    )
    (net (code "62") (name "M1") (class "Default")
      (node (ref "R32") (pin "1") (pinfunction "1_1") (pintype "unspecified"))
      (node (ref "U2") (pin "48") (pinfunction "M2_48") (pintype "bidirectional"))
    )
    (net (code "63") (name "M2") (class "Default")
      (node (ref "R33") (pin "1") (pinfunction "1_1") (pintype "unspecified"))
      (node (ref "U2") (pin "47") (pinfunction "M1_47") (pintype "bidirectional"))
    )
    (net (code "64") (name "Net-(C45-Pad1)") (class "Default")
      (node (ref "C45") (pin "1") (pinfunction "1_1") (pintype "unspecified"))
      (node (ref "R2") (pin "2") (pinfunction "2_2") (pintype "unspecified"))
    )
    (net (code "65") (name "Net-(C45-Pad2)") (class "Default")
      (node (ref "C45") (pin "2") (pinfunction "2_2") (pintype "unspecified"))
      (node (ref "L5") (pin "2") (pinfunction "2_2") (pintype "unspecified"))
    )
    (net (code "66") (name "Net-(C46-Pad2)") (class "Default")
      (node (ref "C46") (pin "2") (pinfunction "2_2") (pintype "unspecified"))
      (node (ref "R37") (pin "2") (pinfunction "2_2") (pintype "unspecified"))
    )
    (net (code "67") (name "Net-(U1-HSYNC)") (class "Default")
      (node (ref "R29") (pin "2") (pinfunction "2_2") (pintype "unspecified"))
      (node (ref "U1") (pin "48") (pinfunction "HSYNC_48") (pintype "unspecified"))
    )
    (net (code "68") (name "Net-(U1-OCK_INV)") (class "Default")
      (node (ref "R31") (pin "1") (pinfunction "1_1") (pintype "unspecified"))
      (node (ref "U1") (pin "100") (pinfunction "OCK_INV_100") (pintype "unspecified"))
    )
    (net (code "69") (name "Net-(U1-ODCK)") (class "Default")
      (node (ref "R30") (pin "2") (pinfunction "2_2") (pintype "unspecified"))
      (node (ref "U1") (pin "44") (pinfunction "ODCK_44") (pintype "unspecified"))
    )
    (net (code "70") (name "Net-(U1-PD#)") (class "Default")
      (node (ref "D1") (pin "1") (pinfunction "1_1") (pintype "unspecified"))
      (node (ref "U1") (pin "2") (pinfunction "PD#_2") (pintype "unspecified"))
    )
    (net (code "71") (name "Net-(U1-PDO#)") (class "Default")
      (node (ref "D2") (pin "1") (pinfunction "1_1") (pintype "unspecified"))
      (node (ref "U1") (pin "9") (pinfunction "PDO#_9") (pintype "unspecified"))
    )
    (net (code "72") (name "Net-(U1-QE0)") (class "Default")
      (node (ref "R3") (pin "2") (pinfunction "2_2") (pintype "unspecified"))
      (node (ref "U1") (pin "10") (pinfunction "QE0_10") (pintype "unspecified"))
    )
    (net (code "73") (name "Net-(U1-QE1)") (class "Default")
      (node (ref "R4") (pin "2") (pinfunction "2_2") (pintype "unspecified"))
      (node (ref "U1") (pin "11") (pinfunction "QE1_11") (pintype "unspecified"))
    )
    (net (code "74") (name "Net-(U1-QE2)") (class "Default")
      (node (ref "R5") (pin "2") (pinfunction "2_2") (pintype "unspecified"))
      (node (ref "U1") (pin "12") (pinfunction "QE2_12") (pintype "unspecified"))
    )
    (net (code "75") (name "Net-(U1-QE3)") (class "Default")
      (node (ref "R7") (pin "2") (pinfunction "2_2") (pintype "unspecified"))
      (node (ref "U1") (pin "13") (pinfunction "QE3_13") (pintype "unspecified"))
    )
    (net (code "76") (name "Net-(U1-QE4)") (class "Default")
      (node (ref "R6") (pin "2") (pinfunction "2_2") (pintype "unspecified"))
      (node (ref "U1") (pin "14") (pinfunction "QE4_14") (pintype "unspecified"))
    )
    (net (code "77") (name "Net-(U1-QE5)") (class "Default")
      (node (ref "R9") (pin "2") (pinfunction "2_2") (pintype "unspecified"))
      (node (ref "U1") (pin "15") (pinfunction "QE5_15") (pintype "unspecified"))
    )
    (net (code "78") (name "Net-(U1-QE6)") (class "Default")
      (node (ref "R8") (pin "2") (pinfunction "2_2") (pintype "unspecified"))
      (node (ref "U1") (pin "16") (pinfunction "QE6_16") (pintype "unspecified"))
    )
    (net (code "79") (name "Net-(U1-QE7)") (class "Default")
      (node (ref "R10") (pin "2") (pinfunction "2_2") (pintype "unspecified"))
      (node (ref "U1") (pin "17") (pinfunction "QE7_17") (pintype "unspecified"))
    )
    (net (code "80") (name "Net-(U1-QE8)") (class "Default")
      (node (ref "R18") (pin "2") (pinfunction "2_2") (pintype "unspecified"))
      (node (ref "U1") (pin "20") (pinfunction "QE8_20") (pintype "unspecified"))
    )
    (net (code "81") (name "Net-(U1-QE9)") (class "Default")
      (node (ref "R17") (pin "2") (pinfunction "2_2") (pintype "unspecified"))
      (node (ref "U1") (pin "21") (pinfunction "QE9_21") (pintype "unspecified"))
    )
    (net (code "82") (name "Net-(U1-QE10)") (class "Default")
      (node (ref "R16") (pin "2") (pinfunction "2_2") (pintype "unspecified"))
      (node (ref "U1") (pin "22") (pinfunction "QE10_22") (pintype "unspecified"))
    )
    (net (code "83") (name "Net-(U1-QE11)") (class "Default")
      (node (ref "R14") (pin "2") (pinfunction "2_2") (pintype "unspecified"))
      (node (ref "U1") (pin "23") (pinfunction "QE11_23") (pintype "unspecified"))
    )
    (net (code "84") (name "Net-(U1-QE12)") (class "Default")
      (node (ref "R15") (pin "2") (pinfunction "2_2") (pintype "unspecified"))
      (node (ref "U1") (pin "24") (pinfunction "QE12_24") (pintype "unspecified"))
    )
    (net (code "85") (name "Net-(U1-QE13)") (class "Default")
      (node (ref "R12") (pin "2") (pinfunction "2_2") (pintype "unspecified"))
      (node (ref "U1") (pin "25") (pinfunction "QE13_25") (pintype "unspecified"))
    )
    (net (code "86") (name "Net-(U1-QE14)") (class "Default")
      (node (ref "R13") (pin "2") (pinfunction "2_2") (pintype "unspecified"))
      (node (ref "U1") (pin "26") (pinfunction "QE14_26") (pintype "unspecified"))
    )
    (net (code "87") (name "Net-(U1-QE15)") (class "Default")
      (node (ref "R11") (pin "2") (pinfunction "2_2") (pintype "unspecified"))
      (node (ref "U1") (pin "27") (pinfunction "QE15_27") (pintype "unspecified"))
    )
    (net (code "88") (name "Net-(U1-QE16)") (class "Default")
      (node (ref "R26") (pin "2") (pinfunction "2_2") (pintype "unspecified"))
      (node (ref "U1") (pin "30") (pinfunction "QE16_30") (pintype "unspecified"))
    )
    (net (code "89") (name "Net-(U1-QE17)") (class "Default")
      (node (ref "R25") (pin "2") (pinfunction "2_2") (pintype "unspecified"))
      (node (ref "U1") (pin "31") (pinfunction "QE17_31") (pintype "unspecified"))
    )
    (net (code "90") (name "Net-(U1-QE18)") (class "Default")
      (node (ref "R24") (pin "2") (pinfunction "2_2") (pintype "unspecified"))
      (node (ref "U1") (pin "32") (pinfunction "QE18_32") (pintype "unspecified"))
    )
    (net (code "91") (name "Net-(U1-QE19)") (class "Default")
      (node (ref "R22") (pin "2") (pinfunction "2_2") (pintype "unspecified"))
      (node (ref "U1") (pin "33") (pinfunction "QE19_33") (pintype "unspecified"))
    )
    (net (code "92") (name "Net-(U1-QE20)") (class "Default")
      (node (ref "R23") (pin "2") (pinfunction "2_2") (pintype "unspecified"))
      (node (ref "U1") (pin "34") (pinfunction "QE20_34") (pintype "unspecified"))
    )
    (net (code "93") (name "Net-(U1-QE21)") (class "Default")
      (node (ref "R20") (pin "2") (pinfunction "2_2") (pintype "unspecified"))
      (node (ref "U1") (pin "35") (pinfunction "QE21_35") (pintype "unspecified"))
    )
    (net (code "94") (name "Net-(U1-QE22)") (class "Default")
      (node (ref "R21") (pin "2") (pinfunction "2_2") (pintype "unspecified"))
      (node (ref "U1") (pin "36") (pinfunction "QE22_36") (pintype "unspecified"))
    )
    (net (code "95") (name "Net-(U1-QE23)") (class "Default")
      (node (ref "R19") (pin "2") (pinfunction "2_2") (pintype "unspecified"))
      (node (ref "U1") (pin "37") (pinfunction "QE23_37") (pintype "unspecified"))
    )
    (net (code "96") (name "Net-(U1-ST)") (class "Default")
      (node (ref "R1") (pin "1") (pinfunction "1_1") (pintype "unspecified"))
      (node (ref "U1") (pin "3") (pinfunction "ST_3") (pintype "unspecified"))
    )
    (net (code "97") (name "Net-(U1-VSYNC)") (class "Default")
      (node (ref "R28") (pin "2") (pinfunction "2_2") (pintype "unspecified"))
      (node (ref "U1") (pin "47") (pinfunction "VSYNC_47") (pintype "unspecified"))
    )
    (net (code "98") (name "Net-(U2-COMP)") (class "Default")
      (node (ref "C12") (pin "1") (pinfunction "1_1") (pintype "unspecified"))
      (node (ref "U2") (pin "39") (pinfunction "COMP_39") (pintype "bidirectional"))
    )
    (net (code "99") (name "Net-(U2-FSADJ)") (class "Default")
      (node (ref "R36") (pin "2") (pinfunction "2_2") (pintype "unspecified"))
      (node (ref "U2") (pin "38") (pinfunction "FSADJ_38") (pintype "bidirectional"))
    )
    (net (code "100") (name "Net-(U3-B)") (class "Default")
      (node (ref "U3") (pin "2") (pinfunction "B_2") (pintype "unspecified"))
      (node (ref "U6") (pin "4") (pinfunction "Y_4") (pintype "unspecified"))
    )
    (net (code "101") (name "Net-(U4-CAPM)") (class "Default")
      (node (ref "C33") (pin "2") (pinfunction "2_2") (pintype "unspecified"))
      (node (ref "U4") (pin "4") (pinfunction "CAPM_4") (pintype "unspecified"))
    )
    (net (code "102") (name "Net-(U4-LDOO)") (class "Default")
      (node (ref "C15") (pin "1") (pinfunction "1_1") (pintype "unspecified"))
      (node (ref "C16") (pin "1") (pinfunction "1_1") (pintype "unspecified"))
      (node (ref "U4") (pin "26") (pinfunction "LDOO_26") (pintype "unspecified"))
    )
    (net (code "103") (name "Net-(U4-VNEG)") (class "Default")
      (node (ref "C34") (pin "2") (pinfunction "2_2") (pintype "unspecified"))
      (node (ref "U4") (pin "5") (pinfunction "VNEG_5") (pintype "unspecified"))
    )
    (net (code "104") (name "Net-(U7-A)") (class "Default")
      (node (ref "U7") (pin "1") (pinfunction "A_1") (pintype "unspecified"))
      (node (ref "U8") (pin "12") (pinfunction "QC_12") (pintype "unspecified"))
    )
    (net (code "105") (name "Net-(U7-B)") (class "Default")
      (node (ref "U7") (pin "2") (pinfunction "B_2") (pintype "unspecified"))
      (node (ref "U8") (pin "11") (pinfunction "QD_11") (pintype "unspecified"))
    )
    (net (code "106") (name "Net-(U12-C1+)") (class "Default")
      (node (ref "C31") (pin "1") (pinfunction "1_1") (pintype "unspecified"))
      (node (ref "U12") (pin "5") (pinfunction "C1+_5") (pintype "unspecified"))
    )
    (net (code "107") (name "Net-(U12-C1-)") (class "Default")
      (node (ref "C31") (pin "2") (pinfunction "2_2") (pintype "unspecified"))
      (node (ref "U12") (pin "6") (pinfunction "C1-_6") (pintype "unspecified"))
    )
    (net (code "108") (name "Net-(U13-INL)") (class "Default")
      (node (ref "R2") (pin "1") (pinfunction "1_1") (pintype "unspecified"))
      (node (ref "U13") (pin "7") (pinfunction "INL_7") (pintype "unspecified"))
    )
    (net (code "109") (name "Net-(U13-VREF)") (class "Default")
      (node (ref "C43") (pin "2") (pinfunction "2_2") (pintype "unspecified"))
      (node (ref "U13") (pin "8") (pinfunction "VREF_8") (pintype "unspecified"))
    )
    (net (code "110") (name "OVDD") (class "Default")
      (node (ref "C3") (pin "2") (pinfunction "2_2") (pintype "unspecified"))
      (node (ref "C4") (pin "2") (pinfunction "2_2") (pintype "unspecified"))
      (node (ref "C5") (pin "2") (pinfunction "2_2") (pintype "unspecified"))
      (node (ref "C6") (pin "2") (pinfunction "2_2") (pintype "unspecified"))
      (node (ref "L3") (pin "1") (pinfunction "1_1") (pintype "unspecified"))
      (node (ref "U1") (pin "18") (pinfunction "OVDD_18") (pintype "unspecified"))
      (node (ref "U1") (pin "29") (pinfunction "OVDD_29") (pintype "unspecified"))
      (node (ref "U1") (pin "43") (pinfunction "OVDD_43") (pintype "unspecified"))
      (node (ref "U1") (pin "57") (pinfunction "OVDD_57") (pintype "unspecified"))
      (node (ref "U1") (pin "78") (pinfunction "OVDD_78") (pintype "unspecified"))
    )
    (net (code "111") (name "PRE_OUT_L") (class "Default")
      (node (ref "R42") (pin "2") (pinfunction "2_2") (pintype "unspecified"))
      (node (ref "U4") (pin "6") (pinfunction "OUTL_6") (pintype "unspecified"))
    )
    (net (code "112") (name "PRE_OUT_R") (class "Default")
      (node (ref "R43") (pin "2") (pinfunction "2_2") (pintype "unspecified"))
      (node (ref "U4") (pin "7") (pinfunction "OUTR_7") (pintype "unspecified"))
    )
    (net (code "113") (name "PRE_SPDIF_OUT") (class "Default")
      (node (ref "C46") (pin "1") (pinfunction "1_1") (pintype "unspecified"))
      (node (ref "U5") (pin "18") (pinfunction "TX+_18") (pintype "unspecified"))
    )
    (net (code "114") (name "PRE_TEL_OUT_L+") (class "Default")
      (node (ref "L6") (pin "1") (pinfunction "1_1") (pintype "unspecified"))
      (node (ref "U13") (pin "1") (pinfunction "+OUT_L_1") (pintype "unspecified"))
    )
    (net (code "115") (name "PRE_TEL_OUT_L-") (class "Default")
      (node (ref "L7") (pin "1") (pinfunction "1_1") (pintype "unspecified"))
      (node (ref "U13") (pin "3") (pinfunction "-OUT_L_3") (pintype "unspecified"))
    )
    (net (code "116") (name "PVDD") (class "Default")
      (node (ref "C9") (pin "2") (pinfunction "2_2") (pintype "unspecified"))
      (node (ref "L4") (pin "1") (pinfunction "1_1") (pintype "unspecified"))
      (node (ref "U1") (pin "97") (pinfunction "PVDD_97") (pintype "unspecified"))
    )
    (net (code "117") (name "PWR_ON") (class "Default")
      (node (ref "D1") (pin "2") (pinfunction "2_2") (pintype "unspecified"))
      (node (ref "D2") (pin "2") (pinfunction "2_2") (pintype "unspecified"))
    )
    (net (code "118") (name "SCL") (class "Default")
      (node (ref "R35") (pin "2") (pinfunction "2_2") (pintype "unspecified"))
    )
    (net (code "119") (name "SDA") (class "Default")
      (node (ref "R34") (pin "2") (pinfunction "2_2") (pintype "unspecified"))
    )
    (net (code "120") (name "SPDIF_OUT") (class "Default")
      (node (ref "R37") (pin "1") (pinfunction "1_1") (pintype "unspecified"))
      (node (ref "R41") (pin "1") (pinfunction "1_1") (pintype "unspecified"))
    )
    (net (code "121") (name "SPDIF_RST") (class "Default")
      (node (ref "U5") (pin "15") (pinfunction "RST#_15") (pintype "unspecified"))
    )
    (net (code "122") (name "SPKR_OUT_L") (class "Default")
      (node (ref "C47") (pin "2") (pinfunction "2_2") (pintype "unspecified"))
      (node (ref "R42") (pin "1") (pinfunction "1_1") (pintype "unspecified"))
    )
    (net (code "123") (name "SPKR_OUT_R") (class "Default")
      (node (ref "C48") (pin "2") (pinfunction "2_2") (pintype "unspecified"))
      (node (ref "R43") (pin "1") (pinfunction "1_1") (pintype "unspecified"))
    )
    (net (code "124") (name "SYNC") (class "Default")
      (node (ref "U2") (pin "24") (pinfunction "!SYNC_24") (pintype "bidirectional"))
      (node (ref "U3") (pin "4") (pinfunction "Y_4") (pintype "unspecified"))
    )
    (net (code "125") (name "TEL_AMP_SHDN") (class "Default")
      (node (ref "U13") (pin "12") (pinfunction "SHDN#_12") (pintype "unspecified"))
    )
    (net (code "126") (name "TEL_OUT_L+") (class "Default")
      (node (ref "C49") (pin "1") (pinfunction "1_1") (pintype "unspecified"))
      (node (ref "L6") (pin "2") (pinfunction "2_2") (pintype "unspecified"))
    )
    (net (code "127") (name "TEL_OUT_L-") (class "Default")
      (node (ref "C50") (pin "1") (pinfunction "1_1") (pintype "unspecified"))
      (node (ref "L7") (pin "2") (pinfunction "2_2") (pintype "unspecified"))
    )
    (net (code "128") (name "unconnected-(R27-Pad1)") (class "Default")
      (node (ref "R27") (pin "1") (pinfunction "1_1") (pintype "unspecified+no_connect"))
    )
    (net (code "129") (name "unconnected-(U1-CTL1-Pad40)") (class "Default")
      (node (ref "U1") (pin "40") (pinfunction "CTL1_40") (pintype "unspecified+no_connect"))
    )
    (net (code "130") (name "unconnected-(U1-CTL2-Pad41)") (class "Default")
      (node (ref "U1") (pin "41") (pinfunction "CTL2_41") (pintype "unspecified+no_connect"))
    )
    (net (code "131") (name "unconnected-(U1-CTL3-Pad42)") (class "Default")
      (node (ref "U1") (pin "42") (pinfunction "CTL3_42") (pintype "unspecified+no_connect"))
    )
    (net (code "132") (name "unconnected-(U1-EXT_RES-Pad96)") (class "Default")
      (node (ref "U1") (pin "96") (pinfunction "EXT_RES_96") (pintype "unspecified+no_connect"))
    )
    (net (code "133") (name "unconnected-(U1-QO0-Pad49)") (class "Default")
      (node (ref "U1") (pin "49") (pinfunction "QO0_49") (pintype "unspecified+no_connect"))
    )
    (net (code "134") (name "unconnected-(U1-QO1-Pad50)") (class "Default")
      (node (ref "U1") (pin "50") (pinfunction "QO1_50") (pintype "unspecified+no_connect"))
    )
    (net (code "135") (name "unconnected-(U1-QO2-Pad51)") (class "Default")
      (node (ref "U1") (pin "51") (pinfunction "QO2_51") (pintype "unspecified+no_connect"))
    )
    (net (code "136") (name "unconnected-(U1-QO3-Pad52)") (class "Default")
      (node (ref "U1") (pin "52") (pinfunction "QO3_52") (pintype "unspecified+no_connect"))
    )
    (net (code "137") (name "unconnected-(U1-QO4-Pad53)") (class "Default")
      (node (ref "U1") (pin "53") (pinfunction "QO4_53") (pintype "unspecified+no_connect"))
    )
    (net (code "138") (name "unconnected-(U1-QO5-Pad54)") (class "Default")
      (node (ref "U1") (pin "54") (pinfunction "QO5_54") (pintype "unspecified+no_connect"))
    )
    (net (code "139") (name "unconnected-(U1-QO6-Pad55)") (class "Default")
      (node (ref "U1") (pin "55") (pinfunction "QO6_55") (pintype "unspecified+no_connect"))
    )
    (net (code "140") (name "unconnected-(U1-QO7-Pad56)") (class "Default")
      (node (ref "U1") (pin "56") (pinfunction "QO7_56") (pintype "unspecified+no_connect"))
    )
    (net (code "141") (name "unconnected-(U1-QO8-Pad59)") (class "Default")
      (node (ref "U1") (pin "59") (pinfunction "QO8_59") (pintype "unspecified+no_connect"))
    )
    (net (code "142") (name "unconnected-(U1-QO9-Pad60)") (class "Default")
      (node (ref "U1") (pin "60") (pinfunction "QO9_60") (pintype "unspecified+no_connect"))
    )
    (net (code "143") (name "unconnected-(U1-QO10-Pad61)") (class "Default")
      (node (ref "U1") (pin "61") (pinfunction "QO10_61") (pintype "unspecified+no_connect"))
    )
    (net (code "144") (name "unconnected-(U1-QO11-Pad62)") (class "Default")
      (node (ref "U1") (pin "62") (pinfunction "QO11_62") (pintype "unspecified+no_connect"))
    )
    (net (code "145") (name "unconnected-(U1-QO12-Pad63)") (class "Default")
      (node (ref "U1") (pin "63") (pinfunction "QO12_63") (pintype "unspecified+no_connect"))
    )
    (net (code "146") (name "unconnected-(U1-QO13-Pad64)") (class "Default")
      (node (ref "U1") (pin "64") (pinfunction "QO13_64") (pintype "unspecified+no_connect"))
    )
    (net (code "147") (name "unconnected-(U1-QO14-Pad65)") (class "Default")
      (node (ref "U1") (pin "65") (pinfunction "QO14_65") (pintype "unspecified+no_connect"))
    )
    (net (code "148") (name "unconnected-(U1-QO15-Pad66)") (class "Default")
      (node (ref "U1") (pin "66") (pinfunction "QO15_66") (pintype "unspecified+no_connect"))
    )
    (net (code "149") (name "unconnected-(U1-QO16-Pad69)") (class "Default")
      (node (ref "U1") (pin "69") (pinfunction "QO16_69") (pintype "unspecified+no_connect"))
    )
    (net (code "150") (name "unconnected-(U1-QO17-Pad70)") (class "Default")
      (node (ref "U1") (pin "70") (pinfunction "QO17_70") (pintype "unspecified+no_connect"))
    )
    (net (code "151") (name "unconnected-(U1-QO18-Pad71)") (class "Default")
      (node (ref "U1") (pin "71") (pinfunction "QO18_71") (pintype "unspecified+no_connect"))
    )
    (net (code "152") (name "unconnected-(U1-QO19-Pad72)") (class "Default")
      (node (ref "U1") (pin "72") (pinfunction "QO19_72") (pintype "unspecified+no_connect"))
    )
    (net (code "153") (name "unconnected-(U1-QO20-Pad73)") (class "Default")
      (node (ref "U1") (pin "73") (pinfunction "QO20_73") (pintype "unspecified+no_connect"))
    )
    (net (code "154") (name "unconnected-(U1-QO21-Pad74)") (class "Default")
      (node (ref "U1") (pin "74") (pinfunction "QO21_74") (pintype "unspecified+no_connect"))
    )
    (net (code "155") (name "unconnected-(U1-QO22-Pad75)") (class "Default")
      (node (ref "U1") (pin "75") (pinfunction "QO22_75") (pintype "unspecified+no_connect"))
    )
    (net (code "156") (name "unconnected-(U1-QO23-Pad77)") (class "Default")
      (node (ref "U1") (pin "77") (pinfunction "QO23_77") (pintype "unspecified+no_connect"))
    )
    (net (code "157") (name "unconnected-(U2-!BLANK-Pad23)") (class "Default")
      (node (ref "U2") (pin "23") (pinfunction "!BLANK_23") (pintype "bidirectional+no_connect"))
    )
    (net (code "158") (name "unconnected-(U2-VREF-Pad37)") (class "Default")
      (node (ref "U2") (pin "37") (pinfunction "VREF_37") (pintype "bidirectional+no_connect"))
    )
    (net (code "159") (name "unconnected-(U4-GPIO3-Pad15)") (class "Default")
      (node (ref "U4") (pin "15") (pinfunction "GPIO3_15") (pintype "unspecified+no_connect"))
    )
    (net (code "160") (name "unconnected-(U4-GPIO4-Pad14)") (class "Default")
      (node (ref "U4") (pin "14") (pinfunction "GPIO4_14") (pintype "unspecified+no_connect"))
    )
    (net (code "161") (name "unconnected-(U4-GPIO5-Pad13)") (class "Default")
      (node (ref "U4") (pin "13") (pinfunction "GPIO5_13") (pintype "unspecified+no_connect"))
    )
    (net (code "162") (name "unconnected-(U4-GPIO6-Pad19)") (class "Default")
      (node (ref "U4") (pin "19") (pinfunction "GPIO6_19") (pintype "unspecified+no_connect"))
    )
    (net (code "163") (name "unconnected-(U5-BLS-Pad25)") (class "Default")
      (node (ref "U5") (pin "25") (pinfunction "BLS_25") (pintype "unspecified+no_connect"))
    )
    (net (code "164") (name "unconnected-(U5-TX--Pad17)") (class "Default")
      (node (ref "U5") (pin "17") (pinfunction "TX-_17") (pintype "unspecified+no_connect"))
    )
    (net (code "165") (name "unconnected-(U8-QA-Pad14)") (class "Default")
      (node (ref "U8") (pin "14") (pinfunction "QA_14") (pintype "unspecified+no_connect"))
    )
    (net (code "166") (name "unconnected-(U8-QB-Pad13)") (class "Default")
      (node (ref "U8") (pin "13") (pinfunction "QB_13") (pintype "unspecified+no_connect"))
    )
    (net (code "167") (name "unconnected-(U8-RCO-Pad15)") (class "Default")
      (node (ref "U8") (pin "15") (pinfunction "RCO_15") (pintype "unspecified+no_connect"))
    )
    (net (code "168") (name "unconnected-(U12-EN-Pad4)") (class "Default")
      (node (ref "U12") (pin "4") (pinfunction "EN_4") (pintype "unspecified+no_connect"))
    )
    (net (code "169") (name "unconnected-(U13-+OUT_R-Pad16)") (class "Default")
      (node (ref "U13") (pin "16") (pinfunction "+OUT_R_16") (pintype "unspecified+no_connect"))
    )
    (net (code "170") (name "unconnected-(U13--OUT_R-Pad14)") (class "Default")
      (node (ref "U13") (pin "14") (pinfunction "-OUT_R_14") (pintype "unspecified+no_connect"))
    )
    (net (code "171") (name "unconnected-(U13-MUTE#-Pad5)") (class "Default")
      (node (ref "U13") (pin "5") (pinfunction "MUTE#_5") (pintype "unspecified+no_connect"))
    )
  )
)
